# CurrentMetterLEDScreen.net
KiCad netlist of a schematic drawn in EAGLE
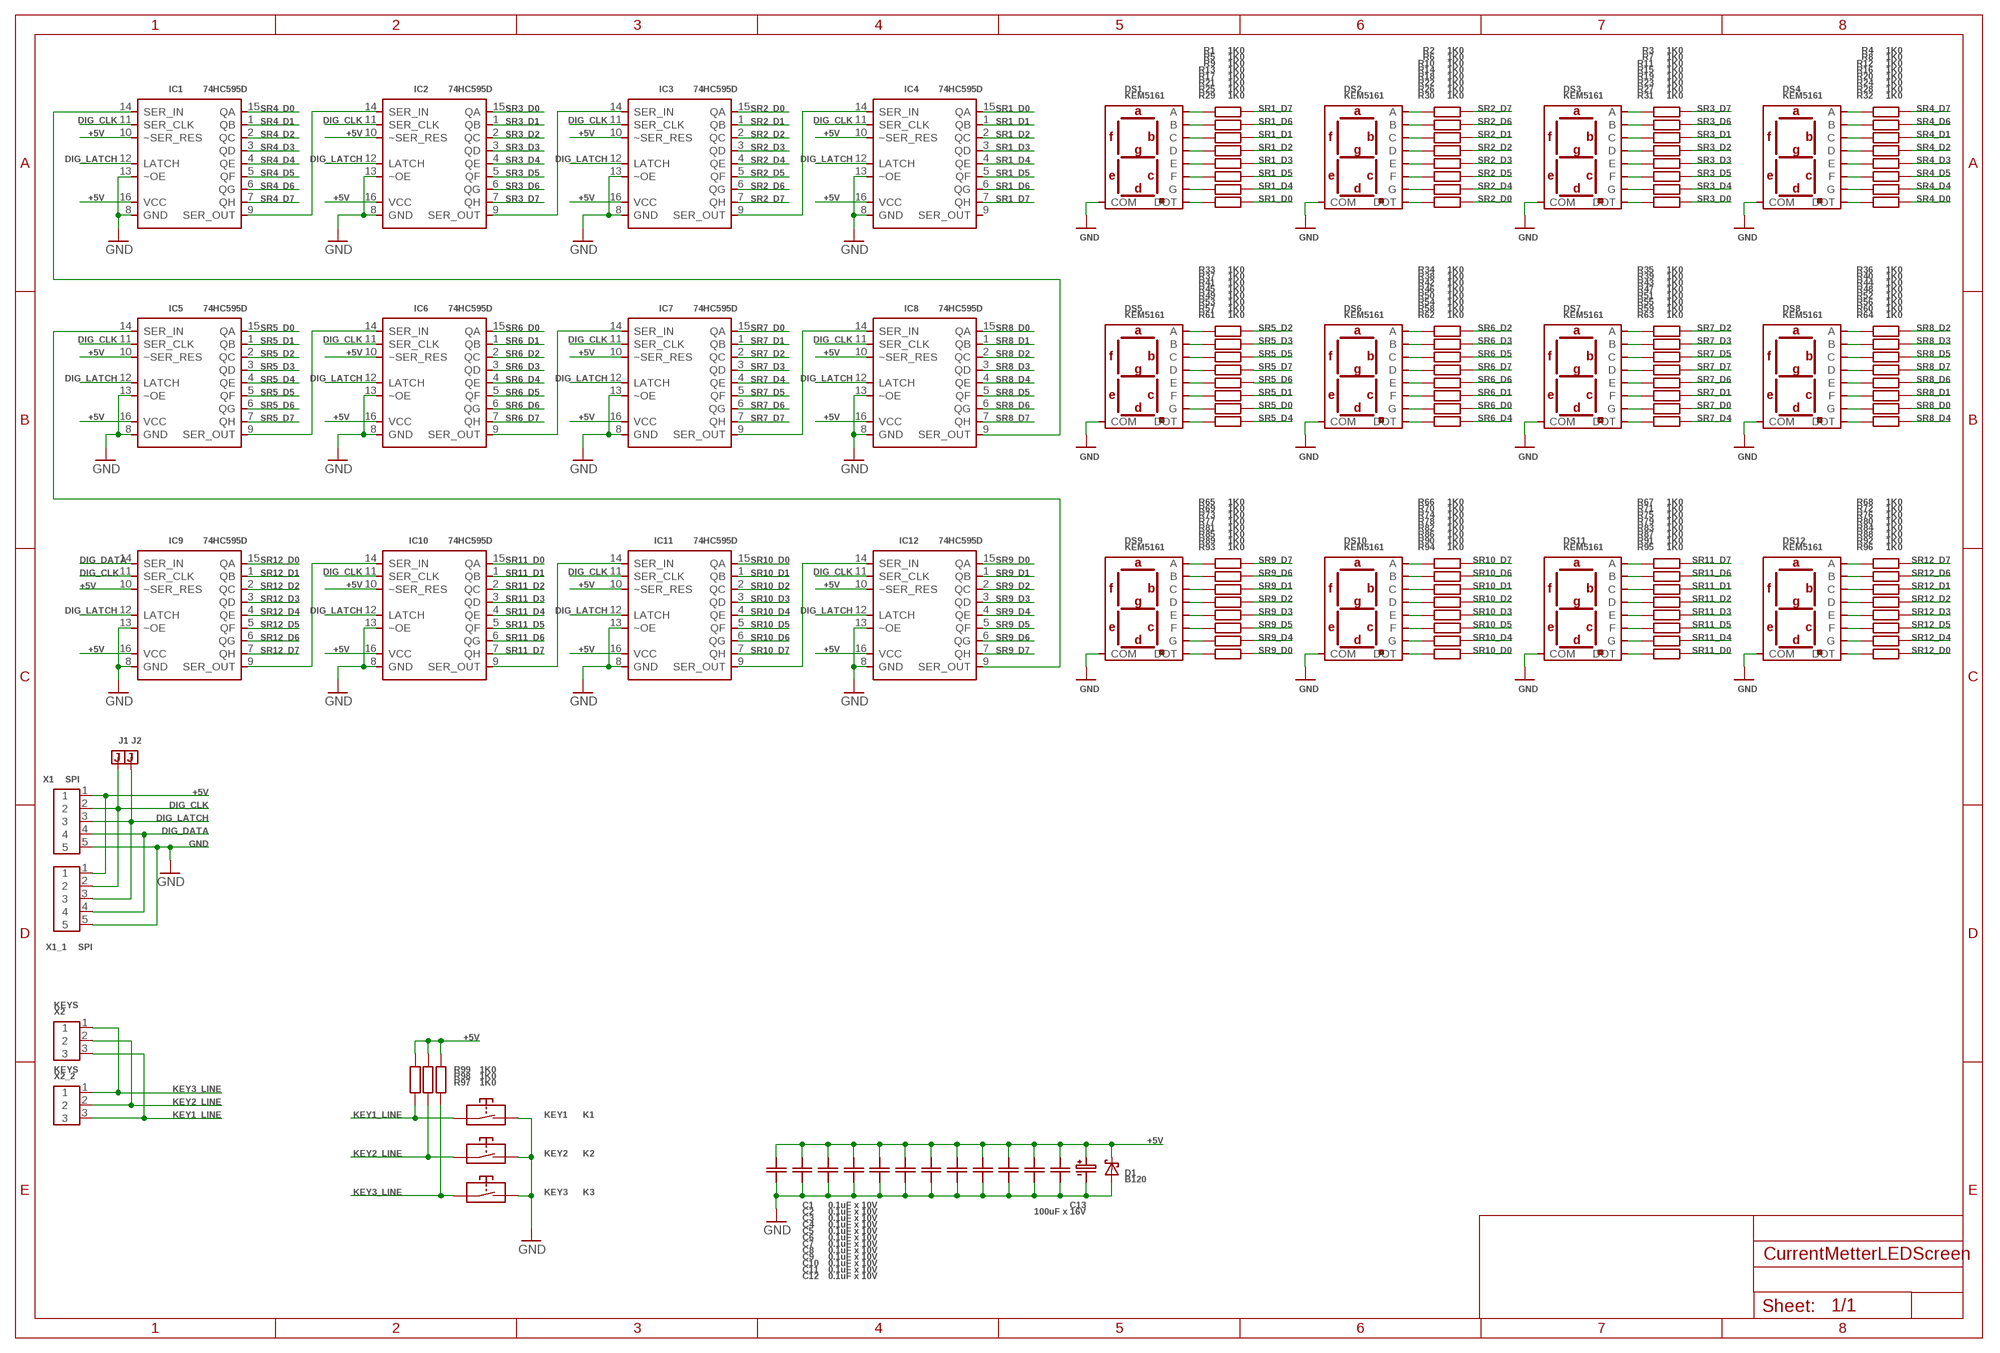
[diagram p0: schematic, sheet 1]

(export (version "E")
  (design (tool "Eeschema 10.0.6"))
  (components
    (comp (ref "C1")
      (value "0.1uF x 10V")
      (footprint "eagle-import:RSMD_0603")
      (libsource (lib "eagle-import") (part "CSMD_0603"))
    )
    (comp (ref "C2")
      (value "0.1uF x 10V")
      (footprint "eagle-import:RSMD_0603")
      (libsource (lib "eagle-import") (part "CSMD_0603"))
    )
    (comp (ref "C3")
      (value "0.1uF x 10V")
      (footprint "eagle-import:RSMD_0603")
      (libsource (lib "eagle-import") (part "CSMD_0603"))
    )
    (comp (ref "C4")
      (value "0.1uF x 10V")
      (footprint "eagle-import:RSMD_0603")
      (libsource (lib "eagle-import") (part "CSMD_0603"))
    )
    (comp (ref "C5")
      (value "0.1uF x 10V")
      (footprint "eagle-import:RSMD_0603")
      (libsource (lib "eagle-import") (part "CSMD_0603"))
    )
    (comp (ref "C6")
      (value "0.1uF x 10V")
      (footprint "eagle-import:RSMD_0603")
      (libsource (lib "eagle-import") (part "CSMD_0603"))
    )
    (comp (ref "C7")
      (value "0.1uF x 10V")
      (footprint "eagle-import:RSMD_0603")
      (libsource (lib "eagle-import") (part "CSMD_0603"))
    )
    (comp (ref "C8")
      (value "0.1uF x 10V")
      (footprint "eagle-import:RSMD_0603")
      (libsource (lib "eagle-import") (part "CSMD_0603"))
    )
    (comp (ref "C9")
      (value "0.1uF x 10V")
      (footprint "eagle-import:RSMD_0603")
      (libsource (lib "eagle-import") (part "CSMD_0603"))
    )
    (comp (ref "C10")
      (value "0.1uF x 10V")
      (footprint "eagle-import:RSMD_0603")
      (libsource (lib "eagle-import") (part "CSMD_0603"))
    )
    (comp (ref "C11")
      (value "0.1uF x 10V")
      (footprint "eagle-import:RSMD_0603")
      (libsource (lib "eagle-import") (part "CSMD_0603"))
    )
    (comp (ref "C12")
      (value "0.1uF x 10V")
      (footprint "eagle-import:RSMD_0603")
      (libsource (lib "eagle-import") (part "CSMD_0603"))
    )
    (comp (ref "C13")
      (value "100uF x 16V")
      (footprint "eagle-import:CE_6.3MM_HOR_REVERTED")
      (libsource (lib "eagle-import") (part "CE6.3MM_HOR_REVERTED"))
    )
    (comp (ref "D1")
      (value "B120")
      (footprint "eagle-import:DO-214AC")
      (libsource (lib "eagle-import") (part "B120(DO-214AC)"))
    )
    (comp (ref "DS1")
      (value "KEM5161")
      (footprint "eagle-import:KEM-5161(NARROW_PADS_OUTSIDE)")
      (libsource (lib "eagle-import") (part "KEM5161(NARROW_PADS_OUTSIDE)"))
    )
    (comp (ref "DS2")
      (value "KEM5161")
      (footprint "eagle-import:KEM-5161(NARROW_PADS_OUTSIDE)")
      (libsource (lib "eagle-import") (part "KEM5161(NARROW_PADS_OUTSIDE)"))
    )
    (comp (ref "DS3")
      (value "KEM5161")
      (footprint "eagle-import:KEM-5161(NARROW_PADS_OUTSIDE)")
      (libsource (lib "eagle-import") (part "KEM5161(NARROW_PADS_OUTSIDE)"))
    )
    (comp (ref "DS4")
      (value "KEM5161")
      (footprint "eagle-import:KEM-5161(NARROW_PADS_OUTSIDE)")
      (libsource (lib "eagle-import") (part "KEM5161(NARROW_PADS_OUTSIDE)"))
    )
    (comp (ref "DS5")
      (value "KEM5161")
      (footprint "eagle-import:KEM-5161(NARROW_PADS_OUTSIDE)")
      (libsource (lib "eagle-import") (part "KEM5161(NARROW_PADS_OUTSIDE)"))
    )
    (comp (ref "DS6")
      (value "KEM5161")
      (footprint "eagle-import:KEM-5161(NARROW_PADS_OUTSIDE)")
      (libsource (lib "eagle-import") (part "KEM5161(NARROW_PADS_OUTSIDE)"))
    )
    (comp (ref "DS7")
      (value "KEM5161")
      (footprint "eagle-import:KEM-5161(NARROW_PADS_OUTSIDE)")
      (libsource (lib "eagle-import") (part "KEM5161(NARROW_PADS_OUTSIDE)"))
    )
    (comp (ref "DS8")
      (value "KEM5161")
      (footprint "eagle-import:KEM-5161(NARROW_PADS_OUTSIDE)")
      (libsource (lib "eagle-import") (part "KEM5161(NARROW_PADS_OUTSIDE)"))
    )
    (comp (ref "DS9")
      (value "KEM5161")
      (footprint "eagle-import:KEM-5161(NARROW_PADS_OUTSIDE)")
      (libsource (lib "eagle-import") (part "KEM5161(NARROW_PADS_OUTSIDE)"))
    )
    (comp (ref "DS10")
      (value "KEM5161")
      (footprint "eagle-import:KEM-5161(NARROW_PADS_OUTSIDE)")
      (libsource (lib "eagle-import") (part "KEM5161(NARROW_PADS_OUTSIDE)"))
    )
    (comp (ref "DS11")
      (value "KEM5161")
      (footprint "eagle-import:KEM-5161(NARROW_PADS_OUTSIDE)")
      (libsource (lib "eagle-import") (part "KEM5161(NARROW_PADS_OUTSIDE)"))
    )
    (comp (ref "DS12")
      (value "KEM5161")
      (footprint "eagle-import:KEM-5161(NARROW_PADS_OUTSIDE)")
      (libsource (lib "eagle-import") (part "KEM5161(NARROW_PADS_OUTSIDE)"))
    )
    (comp (ref "IC1")
      (value "74HC595D")
      (footprint "eagle-import:SOIC16")
      (libsource (lib "eagle-import") (part "74HC595(SOIC16)"))
    )
    (comp (ref "IC2")
      (value "74HC595D")
      (footprint "eagle-import:SOIC16")
      (libsource (lib "eagle-import") (part "74HC595(SOIC16)"))
    )
    (comp (ref "IC3")
      (value "74HC595D")
      (footprint "eagle-import:SOIC16")
      (libsource (lib "eagle-import") (part "74HC595(SOIC16)"))
    )
    (comp (ref "IC4")
      (value "74HC595D")
      (footprint "eagle-import:SOIC16")
      (libsource (lib "eagle-import") (part "74HC595(SOIC16)"))
    )
    (comp (ref "IC5")
      (value "74HC595D")
      (footprint "eagle-import:SOIC16")
      (libsource (lib "eagle-import") (part "74HC595(SOIC16)"))
    )
    (comp (ref "IC6")
      (value "74HC595D")
      (footprint "eagle-import:SOIC16")
      (libsource (lib "eagle-import") (part "74HC595(SOIC16)"))
    )
    (comp (ref "IC7")
      (value "74HC595D")
      (footprint "eagle-import:SOIC16")
      (libsource (lib "eagle-import") (part "74HC595(SOIC16)"))
    )
    (comp (ref "IC8")
      (value "74HC595D")
      (footprint "eagle-import:SOIC16")
      (libsource (lib "eagle-import") (part "74HC595(SOIC16)"))
    )
    (comp (ref "IC9")
      (value "74HC595D")
      (footprint "eagle-import:SOIC16")
      (libsource (lib "eagle-import") (part "74HC595(SOIC16)"))
    )
    (comp (ref "IC10")
      (value "74HC595D")
      (footprint "eagle-import:SOIC16")
      (libsource (lib "eagle-import") (part "74HC595(SOIC16)"))
    )
    (comp (ref "IC11")
      (value "74HC595D")
      (footprint "eagle-import:SOIC16")
      (libsource (lib "eagle-import") (part "74HC595(SOIC16)"))
    )
    (comp (ref "IC12")
      (value "74HC595D")
      (footprint "eagle-import:SOIC16")
      (libsource (lib "eagle-import") (part "74HC595(SOIC16)"))
    )
    (comp (ref "J1")
      (value "JUMPER0805")
      (footprint "eagle-import:RSMD_0805")
      (libsource (lib "eagle-import") (part "JUMPER0805"))
    )
    (comp (ref "J2")
      (value "JUMPER0805")
      (footprint "eagle-import:RSMD_0805")
      (libsource (lib "eagle-import") (part "JUMPER0805"))
    )
    (comp (ref "KEY1")
      (value "K1")
      (footprint "eagle-import:KEY_7X4.5_BIG_PADS")
      (libsource (lib "eagle-import") (part "KEY(7X4.5_BIG_PADS)"))
    )
    (comp (ref "KEY2")
      (value "K2")
      (footprint "eagle-import:KEY_7X4.5_BIG_PADS")
      (libsource (lib "eagle-import") (part "KEY(7X4.5_BIG_PADS)"))
    )
    (comp (ref "KEY3")
      (value "K3")
      (footprint "eagle-import:KEY_7X4.5_BIG_PADS")
      (libsource (lib "eagle-import") (part "KEY(7X4.5_BIG_PADS)"))
    )
    (comp (ref "R1")
      (value "1K0")
      (footprint "eagle-import:RSMD_0603")
      (libsource (lib "eagle-import") (part "RSMD_0603"))
    )
    (comp (ref "R2")
      (value "1K0")
      (footprint "eagle-import:RSMD_0603")
      (libsource (lib "eagle-import") (part "RSMD_0603"))
    )
    (comp (ref "R3")
      (value "1K0")
      (footprint "eagle-import:RSMD_0603")
      (libsource (lib "eagle-import") (part "RSMD_0603"))
    )
    (comp (ref "R4")
      (value "1K0")
      (footprint "eagle-import:RSMD_0603")
      (libsource (lib "eagle-import") (part "RSMD_0603"))
    )
    (comp (ref "R5")
      (value "1K0")
      (footprint "eagle-import:RSMD_0603")
      (libsource (lib "eagle-import") (part "RSMD_0603"))
    )
    (comp (ref "R6")
      (value "1K0")
      (footprint "eagle-import:RSMD_0603")
      (libsource (lib "eagle-import") (part "RSMD_0603"))
    )
    (comp (ref "R7")
      (value "1K0")
      (footprint "eagle-import:RSMD_0603")
      (libsource (lib "eagle-import") (part "RSMD_0603"))
    )
    (comp (ref "R8")
      (value "1K0")
      (footprint "eagle-import:RSMD_0603")
      (libsource (lib "eagle-import") (part "RSMD_0603"))
    )
    (comp (ref "R9")
      (value "1K0")
      (footprint "eagle-import:RSMD_0603")
      (libsource (lib "eagle-import") (part "RSMD_0603"))
    )
    (comp (ref "R10")
      (value "1K0")
      (footprint "eagle-import:RSMD_0603")
      (libsource (lib "eagle-import") (part "RSMD_0603"))
    )
    (comp (ref "R11")
      (value "1K0")
      (footprint "eagle-import:RSMD_0603")
      (libsource (lib "eagle-import") (part "RSMD_0603"))
    )
    (comp (ref "R12")
      (value "1K0")
      (footprint "eagle-import:RSMD_0603")
      (libsource (lib "eagle-import") (part "RSMD_0603"))
    )
    (comp (ref "R13")
      (value "1K0")
      (footprint "eagle-import:RSMD_0603")
      (libsource (lib "eagle-import") (part "RSMD_0603"))
    )
    (comp (ref "R14")
      (value "1K0")
      (footprint "eagle-import:RSMD_0603")
      (libsource (lib "eagle-import") (part "RSMD_0603"))
    )
    (comp (ref "R15")
      (value "1K0")
      (footprint "eagle-import:RSMD_0603")
      (libsource (lib "eagle-import") (part "RSMD_0603"))
    )
    (comp (ref "R16")
      (value "1K0")
      (footprint "eagle-import:RSMD_0603")
      (libsource (lib "eagle-import") (part "RSMD_0603"))
    )
    (comp (ref "R17")
      (value "1K0")
      (footprint "eagle-import:RSMD_0603")
      (libsource (lib "eagle-import") (part "RSMD_0603"))
    )
    (comp (ref "R18")
      (value "1K0")
      (footprint "eagle-import:RSMD_0603")
      (libsource (lib "eagle-import") (part "RSMD_0603"))
    )
    (comp (ref "R19")
      (value "1K0")
      (footprint "eagle-import:RSMD_0603")
      (libsource (lib "eagle-import") (part "RSMD_0603"))
    )
    (comp (ref "R20")
      (value "1K0")
      (footprint "eagle-import:RSMD_0603")
      (libsource (lib "eagle-import") (part "RSMD_0603"))
    )
    (comp (ref "R21")
      (value "1K0")
      (footprint "eagle-import:RSMD_0603")
      (libsource (lib "eagle-import") (part "RSMD_0603"))
    )
    (comp (ref "R22")
      (value "1K0")
      (footprint "eagle-import:RSMD_0603")
      (libsource (lib "eagle-import") (part "RSMD_0603"))
    )
    (comp (ref "R23")
      (value "1K0")
      (footprint "eagle-import:RSMD_0603")
      (libsource (lib "eagle-import") (part "RSMD_0603"))
    )
    (comp (ref "R24")
      (value "1K0")
      (footprint "eagle-import:RSMD_0603")
      (libsource (lib "eagle-import") (part "RSMD_0603"))
    )
    (comp (ref "R25")
      (value "1K0")
      (footprint "eagle-import:RSMD_0603")
      (libsource (lib "eagle-import") (part "RSMD_0603"))
    )
    (comp (ref "R26")
      (value "1K0")
      (footprint "eagle-import:RSMD_0603")
      (libsource (lib "eagle-import") (part "RSMD_0603"))
    )
    (comp (ref "R27")
      (value "1K0")
      (footprint "eagle-import:RSMD_0603")
      (libsource (lib "eagle-import") (part "RSMD_0603"))
    )
    (comp (ref "R28")
      (value "1K0")
      (footprint "eagle-import:RSMD_0603")
      (libsource (lib "eagle-import") (part "RSMD_0603"))
    )
    (comp (ref "R29")
      (value "1K0")
      (footprint "eagle-import:RSMD_0603")
      (libsource (lib "eagle-import") (part "RSMD_0603"))
    )
    (comp (ref "R30")
      (value "1K0")
      (footprint "eagle-import:RSMD_0603")
      (libsource (lib "eagle-import") (part "RSMD_0603"))
    )
    (comp (ref "R31")
      (value "1K0")
      (footprint "eagle-import:RSMD_0603")
      (libsource (lib "eagle-import") (part "RSMD_0603"))
    )
    (comp (ref "R32")
      (value "1K0")
      (footprint "eagle-import:RSMD_0603")
      (libsource (lib "eagle-import") (part "RSMD_0603"))
    )
    (comp (ref "R33")
      (value "1K0")
      (footprint "eagle-import:RSMD_0603")
      (libsource (lib "eagle-import") (part "RSMD_0603"))
    )
    (comp (ref "R34")
      (value "1K0")
      (footprint "eagle-import:RSMD_0603")
      (libsource (lib "eagle-import") (part "RSMD_0603"))
    )
    (comp (ref "R35")
      (value "1K0")
      (footprint "eagle-import:RSMD_0603")
      (libsource (lib "eagle-import") (part "RSMD_0603"))
    )
    (comp (ref "R36")
      (value "1K0")
      (footprint "eagle-import:RSMD_0603")
      (libsource (lib "eagle-import") (part "RSMD_0603"))
    )
    (comp (ref "R37")
      (value "1K0")
      (footprint "eagle-import:RSMD_0603")
      (libsource (lib "eagle-import") (part "RSMD_0603"))
    )
    (comp (ref "R38")
      (value "1K0")
      (footprint "eagle-import:RSMD_0603")
      (libsource (lib "eagle-import") (part "RSMD_0603"))
    )
    (comp (ref "R39")
      (value "1K0")
      (footprint "eagle-import:RSMD_0603")
      (libsource (lib "eagle-import") (part "RSMD_0603"))
    )
    (comp (ref "R40")
      (value "1K0")
      (footprint "eagle-import:RSMD_0603")
      (libsource (lib "eagle-import") (part "RSMD_0603"))
    )
    (comp (ref "R41")
      (value "1K0")
      (footprint "eagle-import:RSMD_0603")
      (libsource (lib "eagle-import") (part "RSMD_0603"))
    )
    (comp (ref "R42")
      (value "1K0")
      (footprint "eagle-import:RSMD_0603")
      (libsource (lib "eagle-import") (part "RSMD_0603"))
    )
    (comp (ref "R43")
      (value "1K0")
      (footprint "eagle-import:RSMD_0603")
      (libsource (lib "eagle-import") (part "RSMD_0603"))
    )
    (comp (ref "R44")
      (value "1K0")
      (footprint "eagle-import:RSMD_0603")
      (libsource (lib "eagle-import") (part "RSMD_0603"))
    )
    (comp (ref "R45")
      (value "1K0")
      (footprint "eagle-import:RSMD_0603")
      (libsource (lib "eagle-import") (part "RSMD_0603"))
    )
    (comp (ref "R46")
      (value "1K0")
      (footprint "eagle-import:RSMD_0603")
      (libsource (lib "eagle-import") (part "RSMD_0603"))
    )
    (comp (ref "R47")
      (value "1K0")
      (footprint "eagle-import:RSMD_0603")
      (libsource (lib "eagle-import") (part "RSMD_0603"))
    )
    (comp (ref "R48")
      (value "1K0")
      (footprint "eagle-import:RSMD_0603")
      (libsource (lib "eagle-import") (part "RSMD_0603"))
    )
    (comp (ref "R49")
      (value "1K0")
      (footprint "eagle-import:RSMD_0603")
      (libsource (lib "eagle-import") (part "RSMD_0603"))
    )
    (comp (ref "R50")
      (value "1K0")
      (footprint "eagle-import:RSMD_0603")
      (libsource (lib "eagle-import") (part "RSMD_0603"))
    )
    (comp (ref "R51")
      (value "1K0")
      (footprint "eagle-import:RSMD_0603")
      (libsource (lib "eagle-import") (part "RSMD_0603"))
    )
    (comp (ref "R52")
      (value "1K0")
      (footprint "eagle-import:RSMD_0603")
      (libsource (lib "eagle-import") (part "RSMD_0603"))
    )
    (comp (ref "R53")
      (value "1K0")
      (footprint "eagle-import:RSMD_0603")
      (libsource (lib "eagle-import") (part "RSMD_0603"))
    )
    (comp (ref "R54")
      (value "1K0")
      (footprint "eagle-import:RSMD_0603")
      (libsource (lib "eagle-import") (part "RSMD_0603"))
    )
    (comp (ref "R55")
      (value "1K0")
      (footprint "eagle-import:RSMD_0603")
      (libsource (lib "eagle-import") (part "RSMD_0603"))
    )
    (comp (ref "R56")
      (value "1K0")
      (footprint "eagle-import:RSMD_0603")
      (libsource (lib "eagle-import") (part "RSMD_0603"))
    )
    (comp (ref "R57")
      (value "1K0")
      (footprint "eagle-import:RSMD_0603")
      (libsource (lib "eagle-import") (part "RSMD_0603"))
    )
    (comp (ref "R58")
      (value "1K0")
      (footprint "eagle-import:RSMD_0603")
      (libsource (lib "eagle-import") (part "RSMD_0603"))
    )
    (comp (ref "R59")
      (value "1K0")
      (footprint "eagle-import:RSMD_0603")
      (libsource (lib "eagle-import") (part "RSMD_0603"))
    )
    (comp (ref "R60")
      (value "1K0")
      (footprint "eagle-import:RSMD_0603")
      (libsource (lib "eagle-import") (part "RSMD_0603"))
    )
    (comp (ref "R61")
      (value "1K0")
      (footprint "eagle-import:RSMD_0603")
      (libsource (lib "eagle-import") (part "RSMD_0603"))
    )
    (comp (ref "R62")
      (value "1K0")
      (footprint "eagle-import:RSMD_0603")
      (libsource (lib "eagle-import") (part "RSMD_0603"))
    )
    (comp (ref "R63")
      (value "1K0")
      (footprint "eagle-import:RSMD_0603")
      (libsource (lib "eagle-import") (part "RSMD_0603"))
    )
    (comp (ref "R64")
      (value "1K0")
      (footprint "eagle-import:RSMD_0603")
      (libsource (lib "eagle-import") (part "RSMD_0603"))
    )
    (comp (ref "R65")
      (value "1K0")
      (footprint "eagle-import:RSMD_0603")
      (libsource (lib "eagle-import") (part "RSMD_0603"))
    )
    (comp (ref "R66")
      (value "1K0")
      (footprint "eagle-import:RSMD_0603")
      (libsource (lib "eagle-import") (part "RSMD_0603"))
    )
    (comp (ref "R67")
      (value "1K0")
      (footprint "eagle-import:RSMD_0603")
      (libsource (lib "eagle-import") (part "RSMD_0603"))
    )
    (comp (ref "R68")
      (value "1K0")
      (footprint "eagle-import:RSMD_0603")
      (libsource (lib "eagle-import") (part "RSMD_0603"))
    )
    (comp (ref "R69")
      (value "1K0")
      (footprint "eagle-import:RSMD_0603")
      (libsource (lib "eagle-import") (part "RSMD_0603"))
    )
    (comp (ref "R70")
      (value "1K0")
      (footprint "eagle-import:RSMD_0603")
      (libsource (lib "eagle-import") (part "RSMD_0603"))
    )
    (comp (ref "R71")
      (value "1K0")
      (footprint "eagle-import:RSMD_0603")
      (libsource (lib "eagle-import") (part "RSMD_0603"))
    )
    (comp (ref "R72")
      (value "1K0")
      (footprint "eagle-import:RSMD_0603")
      (libsource (lib "eagle-import") (part "RSMD_0603"))
    )
    (comp (ref "R73")
      (value "1K0")
      (footprint "eagle-import:RSMD_0603")
      (libsource (lib "eagle-import") (part "RSMD_0603"))
    )
    (comp (ref "R74")
      (value "1K0")
      (footprint "eagle-import:RSMD_0603")
      (libsource (lib "eagle-import") (part "RSMD_0603"))
    )
    (comp (ref "R75")
      (value "1K0")
      (footprint "eagle-import:RSMD_0603")
      (libsource (lib "eagle-import") (part "RSMD_0603"))
    )
    (comp (ref "R76")
      (value "1K0")
      (footprint "eagle-import:RSMD_0603")
      (libsource (lib "eagle-import") (part "RSMD_0603"))
    )
    (comp (ref "R77")
      (value "1K0")
      (footprint "eagle-import:RSMD_0603")
      (libsource (lib "eagle-import") (part "RSMD_0603"))
    )
    (comp (ref "R78")
      (value "1K0")
      (footprint "eagle-import:RSMD_0603")
      (libsource (lib "eagle-import") (part "RSMD_0603"))
    )
    (comp (ref "R79")
      (value "1K0")
      (footprint "eagle-import:RSMD_0603")
      (libsource (lib "eagle-import") (part "RSMD_0603"))
    )
    (comp (ref "R80")
      (value "1K0")
      (footprint "eagle-import:RSMD_0603")
      (libsource (lib "eagle-import") (part "RSMD_0603"))
    )
    (comp (ref "R81")
      (value "1K0")
      (footprint "eagle-import:RSMD_0603")
      (libsource (lib "eagle-import") (part "RSMD_0603"))
    )
    (comp (ref "R82")
      (value "1K0")
      (footprint "eagle-import:RSMD_0603")
      (libsource (lib "eagle-import") (part "RSMD_0603"))
    )
    (comp (ref "R83")
      (value "1K0")
      (footprint "eagle-import:RSMD_0603")
      (libsource (lib "eagle-import") (part "RSMD_0603"))
    )
    (comp (ref "R84")
      (value "1K0")
      (footprint "eagle-import:RSMD_0603")
      (libsource (lib "eagle-import") (part "RSMD_0603"))
    )
    (comp (ref "R85")
      (value "1K0")
      (footprint "eagle-import:RSMD_0603")
      (libsource (lib "eagle-import") (part "RSMD_0603"))
    )
    (comp (ref "R86")
      (value "1K0")
      (footprint "eagle-import:RSMD_0603")
      (libsource (lib "eagle-import") (part "RSMD_0603"))
    )
    (comp (ref "R87")
      (value "1K0")
      (footprint "eagle-import:RSMD_0603")
      (libsource (lib "eagle-import") (part "RSMD_0603"))
    )
    (comp (ref "R88")
      (value "1K0")
      (footprint "eagle-import:RSMD_0603")
      (libsource (lib "eagle-import") (part "RSMD_0603"))
    )
    (comp (ref "R89")
      (value "1K0")
      (footprint "eagle-import:RSMD_0603")
      (libsource (lib "eagle-import") (part "RSMD_0603"))
    )
    (comp (ref "R90")
      (value "1K0")
      (footprint "eagle-import:RSMD_0603")
      (libsource (lib "eagle-import") (part "RSMD_0603"))
    )
    (comp (ref "R91")
      (value "1K0")
      (footprint "eagle-import:RSMD_0603")
      (libsource (lib "eagle-import") (part "RSMD_0603"))
    )
    (comp (ref "R92")
      (value "1K0")
      (footprint "eagle-import:RSMD_0603")
      (libsource (lib "eagle-import") (part "RSMD_0603"))
    )
    (comp (ref "R93")
      (value "1K0")
      (footprint "eagle-import:RSMD_0603")
      (libsource (lib "eagle-import") (part "RSMD_0603"))
    )
    (comp (ref "R94")
      (value "1K0")
      (footprint "eagle-import:RSMD_0603")
      (libsource (lib "eagle-import") (part "RSMD_0603"))
    )
    (comp (ref "R95")
      (value "1K0")
      (footprint "eagle-import:RSMD_0603")
      (libsource (lib "eagle-import") (part "RSMD_0603"))
    )
    (comp (ref "R96")
      (value "1K0")
      (footprint "eagle-import:RSMD_0603")
      (libsource (lib "eagle-import") (part "RSMD_0603"))
    )
    (comp (ref "R97")
      (value "1K0")
      (footprint "eagle-import:RSMD_0603")
      (libsource (lib "eagle-import") (part "RSMD_0603"))
    )
    (comp (ref "R98")
      (value "1K0")
      (footprint "eagle-import:RSMD_0603")
      (libsource (lib "eagle-import") (part "RSMD_0603"))
    )
    (comp (ref "R99")
      (value "1K0")
      (footprint "eagle-import:RSMD_0603")
      (libsource (lib "eagle-import") (part "RSMD_0603"))
    )
    (comp (ref "X1")
      (value "SPI")
      (footprint "eagle-import:PIN5X1_2.54MM_SIDE_BOARD")
      (libsource (lib "eagle-import") (part "PIN1X5(2.54_SIDE_BOARD)"))
    )
    (comp (ref "X1_1")
      (value "SPI")
      (footprint "eagle-import:PIN5X1_2.54MM_WITH_CLAMP")
      (libsource (lib "eagle-import") (part "PIN1X5(2.54_VERT_CLAMP)"))
    )
    (comp (ref "X2")
      (value "KEYS")
      (footprint "eagle-import:PIN1X3_2.54MM_SIDE_BOARD")
      (libsource (lib "eagle-import") (part "PIN1X3(2.54MM_SIDE_BOARD)"))
    )
    (comp (ref "X2_2")
      (value "KEYS")
      (footprint "eagle-import:PIN3X1_2.54MM_WITH_CLAMP")
      (libsource (lib "eagle-import") (part "PIN1X3(2.54MM_WITH_CLAMP)"))
    )
  )
  (nets
    (net (code "1") (name "/+5V") (class "Default")
      (node (ref "C1") (pin "PAD_1") (pinfunction "PIN1_PAD_1") (pintype "bidirectional"))
      (node (ref "C10") (pin "PAD_1") (pinfunction "PIN1_PAD_1") (pintype "bidirectional"))
      (node (ref "C11") (pin "PAD_1") (pinfunction "PIN1_PAD_1") (pintype "bidirectional"))
      (node (ref "C12") (pin "PAD_1") (pinfunction "PIN1_PAD_1") (pintype "bidirectional"))
      (node (ref "C13") (pin "PLUS") (pinfunction "PLUS_PLUS") (pintype "bidirectional"))
      (node (ref "C2") (pin "PAD_1") (pinfunction "PIN1_PAD_1") (pintype "bidirectional"))
      (node (ref "C3") (pin "PAD_1") (pinfunction "PIN1_PAD_1") (pintype "bidirectional"))
      (node (ref "C4") (pin "PAD_1") (pinfunction "PIN1_PAD_1") (pintype "bidirectional"))
      (node (ref "C5") (pin "PAD_1") (pinfunction "PIN1_PAD_1") (pintype "bidirectional"))
      (node (ref "C6") (pin "PAD_1") (pinfunction "PIN1_PAD_1") (pintype "bidirectional"))
      (node (ref "C7") (pin "PAD_1") (pinfunction "PIN1_PAD_1") (pintype "bidirectional"))
      (node (ref "C8") (pin "PAD_1") (pinfunction "PIN1_PAD_1") (pintype "bidirectional"))
      (node (ref "C9") (pin "PAD_1") (pinfunction "PIN1_PAD_1") (pintype "bidirectional"))
      (node (ref "D1") (pin "CATHODE") (pinfunction "CATHODE_CATHODE") (pintype "passive"))
      (node (ref "IC1") (pin "10") (pinfunction "~{SER_RES}_10") (pintype "bidirectional"))
      (node (ref "IC1") (pin "16") (pinfunction "VCC_16") (pintype "bidirectional"))
      (node (ref "IC10") (pin "10") (pinfunction "~{SER_RES}_10") (pintype "bidirectional"))
      (node (ref "IC10") (pin "16") (pinfunction "VCC_16") (pintype "bidirectional"))
      (node (ref "IC11") (pin "10") (pinfunction "~{SER_RES}_10") (pintype "bidirectional"))
      (node (ref "IC11") (pin "16") (pinfunction "VCC_16") (pintype "bidirectional"))
      (node (ref "IC12") (pin "10") (pinfunction "~{SER_RES}_10") (pintype "bidirectional"))
      (node (ref "IC12") (pin "16") (pinfunction "VCC_16") (pintype "bidirectional"))
      (node (ref "IC2") (pin "10") (pinfunction "~{SER_RES}_10") (pintype "bidirectional"))
      (node (ref "IC2") (pin "16") (pinfunction "VCC_16") (pintype "bidirectional"))
      (node (ref "IC3") (pin "10") (pinfunction "~{SER_RES}_10") (pintype "bidirectional"))
      (node (ref "IC3") (pin "16") (pinfunction "VCC_16") (pintype "bidirectional"))
      (node (ref "IC4") (pin "10") (pinfunction "~{SER_RES}_10") (pintype "bidirectional"))
      (node (ref "IC4") (pin "16") (pinfunction "VCC_16") (pintype "bidirectional"))
      (node (ref "IC5") (pin "10") (pinfunction "~{SER_RES}_10") (pintype "bidirectional"))
      (node (ref "IC5") (pin "16") (pinfunction "VCC_16") (pintype "bidirectional"))
      (node (ref "IC6") (pin "10") (pinfunction "~{SER_RES}_10") (pintype "bidirectional"))
      (node (ref "IC6") (pin "16") (pinfunction "VCC_16") (pintype "bidirectional"))
      (node (ref "IC7") (pin "10") (pinfunction "~{SER_RES}_10") (pintype "bidirectional"))
      (node (ref "IC7") (pin "16") (pinfunction "VCC_16") (pintype "bidirectional"))
      (node (ref "IC8") (pin "10") (pinfunction "~{SER_RES}_10") (pintype "bidirectional"))
      (node (ref "IC8") (pin "16") (pinfunction "VCC_16") (pintype "bidirectional"))
      (node (ref "IC9") (pin "10") (pinfunction "~{SER_RES}_10") (pintype "bidirectional"))
      (node (ref "IC9") (pin "16") (pinfunction "VCC_16") (pintype "bidirectional"))
      (node (ref "R97") (pin "PAD_1") (pinfunction "PIN1_PAD_1") (pintype "passive"))
      (node (ref "R98") (pin "PAD_1") (pinfunction "PIN1_PAD_1") (pintype "passive"))
      (node (ref "R99") (pin "PAD_1") (pinfunction "PIN1_PAD_1") (pintype "passive"))
      (node (ref "X1") (pin "1") (pinfunction "1_1") (pintype "passive"))
      (node (ref "X1_1") (pin "1") (pinfunction "1_1") (pintype "passive"))
    )
    (net (code "2") (name "/DIG_CLK") (class "Default")
      (node (ref "IC1") (pin "11") (pinfunction "SER_CLK_11") (pintype "bidirectional"))
      (node (ref "IC10") (pin "11") (pinfunction "SER_CLK_11") (pintype "bidirectional"))
      (node (ref "IC11") (pin "11") (pinfunction "SER_CLK_11") (pintype "bidirectional"))
      (node (ref "IC12") (pin "11") (pinfunction "SER_CLK_11") (pintype "bidirectional"))
      (node (ref "IC2") (pin "11") (pinfunction "SER_CLK_11") (pintype "bidirectional"))
      (node (ref "IC3") (pin "11") (pinfunction "SER_CLK_11") (pintype "bidirectional"))
      (node (ref "IC4") (pin "11") (pinfunction "SER_CLK_11") (pintype "bidirectional"))
      (node (ref "IC5") (pin "11") (pinfunction "SER_CLK_11") (pintype "bidirectional"))
      (node (ref "IC6") (pin "11") (pinfunction "SER_CLK_11") (pintype "bidirectional"))
      (node (ref "IC7") (pin "11") (pinfunction "SER_CLK_11") (pintype "bidirectional"))
      (node (ref "IC8") (pin "11") (pinfunction "SER_CLK_11") (pintype "bidirectional"))
      (node (ref "IC9") (pin "11") (pinfunction "SER_CLK_11") (pintype "bidirectional"))
      (node (ref "J1") (pin "PAD_0") (pinfunction "PIN1_PAD_0") (pintype "passive"))
      (node (ref "J1") (pin "PAD_1") (pinfunction "PIN1_PAD_1") (pintype "passive"))
      (node (ref "X1") (pin "2") (pinfunction "2_2") (pintype "passive"))
      (node (ref "X1_1") (pin "2") (pinfunction "2_2") (pintype "passive"))
    )
    (net (code "3") (name "/DIG_DATA") (class "Default")
      (node (ref "IC9") (pin "14") (pinfunction "SER_IN_14") (pintype "bidirectional"))
      (node (ref "X1") (pin "4") (pinfunction "4_4") (pintype "passive"))
      (node (ref "X1_1") (pin "4") (pinfunction "4_4") (pintype "passive"))
    )
    (net (code "4") (name "/DIG_LATCH") (class "Default")
      (node (ref "IC1") (pin "12") (pinfunction "LATCH_12") (pintype "bidirectional"))
      (node (ref "IC10") (pin "12") (pinfunction "LATCH_12") (pintype "bidirectional"))
      (node (ref "IC11") (pin "12") (pinfunction "LATCH_12") (pintype "bidirectional"))
      (node (ref "IC12") (pin "12") (pinfunction "LATCH_12") (pintype "bidirectional"))
      (node (ref "IC2") (pin "12") (pinfunction "LATCH_12") (pintype "bidirectional"))
      (node (ref "IC3") (pin "12") (pinfunction "LATCH_12") (pintype "bidirectional"))
      (node (ref "IC4") (pin "12") (pinfunction "LATCH_12") (pintype "bidirectional"))
      (node (ref "IC5") (pin "12") (pinfunction "LATCH_12") (pintype "bidirectional"))
      (node (ref "IC6") (pin "12") (pinfunction "LATCH_12") (pintype "bidirectional"))
      (node (ref "IC7") (pin "12") (pinfunction "LATCH_12") (pintype "bidirectional"))
      (node (ref "IC8") (pin "12") (pinfunction "LATCH_12") (pintype "bidirectional"))
      (node (ref "IC9") (pin "12") (pinfunction "LATCH_12") (pintype "bidirectional"))
      (node (ref "J2") (pin "PAD_0") (pinfunction "PIN1_PAD_0") (pintype "passive"))
      (node (ref "J2") (pin "PAD_1") (pinfunction "PIN1_PAD_1") (pintype "passive"))
      (node (ref "X1") (pin "3") (pinfunction "3_3") (pintype "passive"))
      (node (ref "X1_1") (pin "3") (pinfunction "3_3") (pintype "passive"))
    )
    (net (code "5") (name "/KEY1_LINE") (class "Default")
      (node (ref "KEY1") (pin "1") (pinfunction "1_1") (pintype "bidirectional"))
      (node (ref "KEY1") (pin "2") (pinfunction "1_2") (pintype "bidirectional"))
      (node (ref "R99") (pin "PAD_0") (pinfunction "PIN0_PAD_0") (pintype "passive"))
      (node (ref "X2") (pin "3") (pinfunction "3_3") (pintype "passive"))
      (node (ref "X2_2") (pin "3") (pinfunction "3_3") (pintype "passive"))
    )
    (net (code "6") (name "/KEY2_LINE") (class "Default")
      (node (ref "KEY2") (pin "1") (pinfunction "1_1") (pintype "bidirectional"))
      (node (ref "KEY2") (pin "2") (pinfunction "1_2") (pintype "bidirectional"))
      (node (ref "R98") (pin "PAD_0") (pinfunction "PIN0_PAD_0") (pintype "passive"))
      (node (ref "X2") (pin "2") (pinfunction "2_2") (pintype "passive"))
      (node (ref "X2_2") (pin "2") (pinfunction "2_2") (pintype "passive"))
    )
    (net (code "7") (name "/KEY3_LINE") (class "Default")
      (node (ref "KEY3") (pin "1") (pinfunction "1_1") (pintype "bidirectional"))
      (node (ref "KEY3") (pin "2") (pinfunction "1_2") (pintype "bidirectional"))
      (node (ref "R97") (pin "PAD_0") (pinfunction "PIN0_PAD_0") (pintype "passive"))
      (node (ref "X2") (pin "1") (pinfunction "1_1") (pintype "passive"))
      (node (ref "X2_2") (pin "1") (pinfunction "1_1") (pintype "passive"))
    )
    (net (code "8") (name "/SR1_D0") (class "Default")
      (node (ref "IC4") (pin "15") (pinfunction "QA_15") (pintype "bidirectional"))
      (node (ref "R29") (pin "PAD_1") (pinfunction "PIN1_PAD_1") (pintype "passive"))
    )
    (net (code "9") (name "/SR1_D1") (class "Default")
      (node (ref "IC4") (pin "1") (pinfunction "QB_1") (pintype "bidirectional"))
      (node (ref "R9") (pin "PAD_1") (pinfunction "PIN1_PAD_1") (pintype "passive"))
    )
    (net (code "10") (name "/SR1_D2") (class "Default")
      (node (ref "IC4") (pin "2") (pinfunction "QC_2") (pintype "bidirectional"))
      (node (ref "R13") (pin "PAD_1") (pinfunction "PIN1_PAD_1") (pintype "passive"))
    )
    (net (code "11") (name "/SR1_D3") (class "Default")
      (node (ref "IC4") (pin "3") (pinfunction "QD_3") (pintype "bidirectional"))
      (node (ref "R17") (pin "PAD_1") (pinfunction "PIN1_PAD_1") (pintype "passive"))
    )
    (net (code "12") (name "/SR1_D4") (class "Default")
      (node (ref "IC4") (pin "4") (pinfunction "QE_4") (pintype "bidirectional"))
      (node (ref "R25") (pin "PAD_1") (pinfunction "PIN1_PAD_1") (pintype "passive"))
    )
    (net (code "13") (name "/SR1_D5") (class "Default")
      (node (ref "IC4") (pin "5") (pinfunction "QF_5") (pintype "bidirectional"))
      (node (ref "R21") (pin "PAD_1") (pinfunction "PIN1_PAD_1") (pintype "passive"))
    )
    (net (code "14") (name "/SR1_D6") (class "Default")
      (node (ref "IC4") (pin "6") (pinfunction "QG_6") (pintype "bidirectional"))
      (node (ref "R5") (pin "PAD_1") (pinfunction "PIN1_PAD_1") (pintype "passive"))
    )
    (net (code "15") (name "/SR1_D7") (class "Default")
      (node (ref "IC4") (pin "7") (pinfunction "QH_7") (pintype "bidirectional"))
      (node (ref "R1") (pin "PAD_1") (pinfunction "PIN1_PAD_1") (pintype "passive"))
    )
    (net (code "16") (name "/SR2_D0") (class "Default")
      (node (ref "IC3") (pin "15") (pinfunction "QA_15") (pintype "bidirectional"))
      (node (ref "R30") (pin "PAD_1") (pinfunction "PIN1_PAD_1") (pintype "passive"))
    )
    (net (code "17") (name "/SR2_D1") (class "Default")
      (node (ref "IC3") (pin "1") (pinfunction "QB_1") (pintype "bidirectional"))
      (node (ref "R10") (pin "PAD_1") (pinfunction "PIN1_PAD_1") (pintype "passive"))
    )
    (net (code "18") (name "/SR2_D2") (class "Default")
      (node (ref "IC3") (pin "2") (pinfunction "QC_2") (pintype "bidirectional"))
      (node (ref "R14") (pin "PAD_1") (pinfunction "PIN1_PAD_1") (pintype "passive"))
    )
    (net (code "19") (name "/SR2_D3") (class "Default")
      (node (ref "IC3") (pin "3") (pinfunction "QD_3") (pintype "bidirectional"))
      (node (ref "R18") (pin "PAD_1") (pinfunction "PIN1_PAD_1") (pintype "passive"))
    )
    (net (code "20") (name "/SR2_D4") (class "Default")
      (node (ref "IC3") (pin "4") (pinfunction "QE_4") (pintype "bidirectional"))
      (node (ref "R26") (pin "PAD_1") (pinfunction "PIN1_PAD_1") (pintype "passive"))
    )
    (net (code "21") (name "/SR2_D5") (class "Default")
      (node (ref "IC3") (pin "5") (pinfunction "QF_5") (pintype "bidirectional"))
      (node (ref "R22") (pin "PAD_1") (pinfunction "PIN1_PAD_1") (pintype "passive"))
    )
    (net (code "22") (name "/SR2_D6") (class "Default")
      (node (ref "IC3") (pin "6") (pinfunction "QG_6") (pintype "bidirectional"))
      (node (ref "R6") (pin "PAD_1") (pinfunction "PIN1_PAD_1") (pintype "passive"))
    )
    (net (code "23") (name "/SR2_D7") (class "Default")
      (node (ref "IC3") (pin "7") (pinfunction "QH_7") (pintype "bidirectional"))
      (node (ref "R2") (pin "PAD_1") (pinfunction "PIN1_PAD_1") (pintype "passive"))
    )
    (net (code "24") (name "/SR3_D0") (class "Default")
      (node (ref "IC2") (pin "15") (pinfunction "QA_15") (pintype "bidirectional"))
      (node (ref "R31") (pin "PAD_1") (pinfunction "PIN1_PAD_1") (pintype "passive"))
    )
    (net (code "25") (name "/SR3_D1") (class "Default")
      (node (ref "IC2") (pin "1") (pinfunction "QB_1") (pintype "bidirectional"))
      (node (ref "R11") (pin "PAD_1") (pinfunction "PIN1_PAD_1") (pintype "passive"))
    )
    (net (code "26") (name "/SR3_D2") (class "Default")
      (node (ref "IC2") (pin "2") (pinfunction "QC_2") (pintype "bidirectional"))
      (node (ref "R15") (pin "PAD_1") (pinfunction "PIN1_PAD_1") (pintype "passive"))
    )
    (net (code "27") (name "/SR3_D3") (class "Default")
      (node (ref "IC2") (pin "3") (pinfunction "QD_3") (pintype "bidirectional"))
      (node (ref "R19") (pin "PAD_1") (pinfunction "PIN1_PAD_1") (pintype "passive"))
    )
    (net (code "28") (name "/SR3_D4") (class "Default")
      (node (ref "IC2") (pin "4") (pinfunction "QE_4") (pintype "bidirectional"))
      (node (ref "R27") (pin "PAD_1") (pinfunction "PIN1_PAD_1") (pintype "passive"))
    )
    (net (code "29") (name "/SR3_D5") (class "Default")
      (node (ref "IC2") (pin "5") (pinfunction "QF_5") (pintype "bidirectional"))
      (node (ref "R23") (pin "PAD_1") (pinfunction "PIN1_PAD_1") (pintype "passive"))
    )
    (net (code "30") (name "/SR3_D6") (class "Default")
      (node (ref "IC2") (pin "6") (pinfunction "QG_6") (pintype "bidirectional"))
      (node (ref "R7") (pin "PAD_1") (pinfunction "PIN1_PAD_1") (pintype "passive"))
    )
    (net (code "31") (name "/SR3_D7") (class "Default")
      (node (ref "IC2") (pin "7") (pinfunction "QH_7") (pintype "bidirectional"))
      (node (ref "R3") (pin "PAD_1") (pinfunction "PIN1_PAD_1") (pintype "passive"))
    )
    (net (code "32") (name "/SR4_D0") (class "Default")
      (node (ref "IC1") (pin "15") (pinfunction "QA_15") (pintype "bidirectional"))
      (node (ref "R32") (pin "PAD_1") (pinfunction "PIN1_PAD_1") (pintype "passive"))
    )
    (net (code "33") (name "/SR4_D1") (class "Default")
      (node (ref "IC1") (pin "1") (pinfunction "QB_1") (pintype "bidirectional"))
      (node (ref "R12") (pin "PAD_1") (pinfunction "PIN1_PAD_1") (pintype "passive"))
    )
    (net (code "34") (name "/SR4_D2") (class "Default")
      (node (ref "IC1") (pin "2") (pinfunction "QC_2") (pintype "bidirectional"))
      (node (ref "R16") (pin "PAD_1") (pinfunction "PIN1_PAD_1") (pintype "passive"))
    )
    (net (code "35") (name "/SR4_D3") (class "Default")
      (node (ref "IC1") (pin "3") (pinfunction "QD_3") (pintype "bidirectional"))
      (node (ref "R20") (pin "PAD_1") (pinfunction "PIN1_PAD_1") (pintype "passive"))
    )
    (net (code "36") (name "/SR4_D4") (class "Default")
      (node (ref "IC1") (pin "4") (pinfunction "QE_4") (pintype "bidirectional"))
      (node (ref "R28") (pin "PAD_1") (pinfunction "PIN1_PAD_1") (pintype "passive"))
    )
    (net (code "37") (name "/SR4_D5") (class "Default")
      (node (ref "IC1") (pin "5") (pinfunction "QF_5") (pintype "bidirectional"))
      (node (ref "R24") (pin "PAD_1") (pinfunction "PIN1_PAD_1") (pintype "passive"))
    )
    (net (code "38") (name "/SR4_D6") (class "Default")
      (node (ref "IC1") (pin "6") (pinfunction "QG_6") (pintype "bidirectional"))
      (node (ref "R8") (pin "PAD_1") (pinfunction "PIN1_PAD_1") (pintype "passive"))
    )
    (net (code "39") (name "/SR4_D7") (class "Default")
      (node (ref "IC1") (pin "7") (pinfunction "QH_7") (pintype "bidirectional"))
      (node (ref "R4") (pin "PAD_1") (pinfunction "PIN1_PAD_1") (pintype "passive"))
    )
    (net (code "40") (name "/SR5_D0") (class "Default")
      (node (ref "IC5") (pin "15") (pinfunction "QA_15") (pintype "bidirectional"))
      (node (ref "R57") (pin "PAD_1") (pinfunction "PIN1_PAD_1") (pintype "passive"))
    )
    (net (code "41") (name "/SR5_D1") (class "Default")
      (node (ref "IC5") (pin "1") (pinfunction "QB_1") (pintype "bidirectional"))
      (node (ref "R53") (pin "PAD_1") (pinfunction "PIN1_PAD_1") (pintype "passive"))
    )
    (net (code "42") (name "/SR5_D2") (class "Default")
      (node (ref "IC5") (pin "2") (pinfunction "QC_2") (pintype "bidirectional"))
      (node (ref "R33") (pin "PAD_1") (pinfunction "PIN1_PAD_1") (pintype "passive"))
    )
    (net (code "43") (name "/SR5_D3") (class "Default")
      (node (ref "IC5") (pin "3") (pinfunction "QD_3") (pintype "bidirectional"))
      (node (ref "R37") (pin "PAD_1") (pinfunction "PIN1_PAD_1") (pintype "passive"))
    )
    (net (code "44") (name "/SR5_D4") (class "Default")
      (node (ref "IC5") (pin "4") (pinfunction "QE_4") (pintype "bidirectional"))
      (node (ref "R61") (pin "PAD_1") (pinfunction "PIN1_PAD_1") (pintype "passive"))
    )
    (net (code "45") (name "/SR5_D5") (class "Default")
      (node (ref "IC5") (pin "5") (pinfunction "QF_5") (pintype "bidirectional"))
      (node (ref "R41") (pin "PAD_1") (pinfunction "PIN1_PAD_1") (pintype "passive"))
    )
    (net (code "46") (name "/SR5_D6") (class "Default")
      (node (ref "IC5") (pin "6") (pinfunction "QG_6") (pintype "bidirectional"))
      (node (ref "R49") (pin "PAD_1") (pinfunction "PIN1_PAD_1") (pintype "passive"))
    )
    (net (code "47") (name "/SR5_D7") (class "Default")
      (node (ref "IC5") (pin "7") (pinfunction "QH_7") (pintype "bidirectional"))
      (node (ref "R45") (pin "PAD_1") (pinfunction "PIN1_PAD_1") (pintype "passive"))
    )
    (net (code "48") (name "/SR6_D0") (class "Default")
      (node (ref "IC6") (pin "15") (pinfunction "QA_15") (pintype "bidirectional"))
      (node (ref "R58") (pin "PAD_1") (pinfunction "PIN1_PAD_1") (pintype "passive"))
    )
    (net (code "49") (name "/SR6_D1") (class "Default")
      (node (ref "IC6") (pin "1") (pinfunction "QB_1") (pintype "bidirectional"))
      (node (ref "R54") (pin "PAD_1") (pinfunction "PIN1_PAD_1") (pintype "passive"))
    )
    (net (code "50") (name "/SR6_D2") (class "Default")
      (node (ref "IC6") (pin "2") (pinfunction "QC_2") (pintype "bidirectional"))
      (node (ref "R34") (pin "PAD_1") (pinfunction "PIN1_PAD_1") (pintype "passive"))
    )
    (net (code "51") (name "/SR6_D3") (class "Default")
      (node (ref "IC6") (pin "3") (pinfunction "QD_3") (pintype "bidirectional"))
      (node (ref "R38") (pin "PAD_1") (pinfunction "PIN1_PAD_1") (pintype "passive"))
    )
    (net (code "52") (name "/SR6_D4") (class "Default")
      (node (ref "IC6") (pin "4") (pinfunction "QE_4") (pintype "bidirectional"))
      (node (ref "R62") (pin "PAD_1") (pinfunction "PIN1_PAD_1") (pintype "passive"))
    )
    (net (code "53") (name "/SR6_D5") (class "Default")
      (node (ref "IC6") (pin "5") (pinfunction "QF_5") (pintype "bidirectional"))
      (node (ref "R42") (pin "PAD_1") (pinfunction "PIN1_PAD_1") (pintype "passive"))
    )
    (net (code "54") (name "/SR6_D6") (class "Default")
      (node (ref "IC6") (pin "6") (pinfunction "QG_6") (pintype "bidirectional"))
      (node (ref "R50") (pin "PAD_1") (pinfunction "PIN1_PAD_1") (pintype "passive"))
    )
    (net (code "55") (name "/SR6_D7") (class "Default")
      (node (ref "IC6") (pin "7") (pinfunction "QH_7") (pintype "bidirectional"))
      (node (ref "R46") (pin "PAD_1") (pinfunction "PIN1_PAD_1") (pintype "passive"))
    )
    (net (code "56") (name "/SR7_D0") (class "Default")
      (node (ref "IC7") (pin "15") (pinfunction "QA_15") (pintype "bidirectional"))
      (node (ref "R59") (pin "PAD_1") (pinfunction "PIN1_PAD_1") (pintype "passive"))
    )
    (net (code "57") (name "/SR7_D1") (class "Default")
      (node (ref "IC7") (pin "1") (pinfunction "QB_1") (pintype "bidirectional"))
      (node (ref "R55") (pin "PAD_1") (pinfunction "PIN1_PAD_1") (pintype "passive"))
    )
    (net (code "58") (name "/SR7_D2") (class "Default")
      (node (ref "IC7") (pin "2") (pinfunction "QC_2") (pintype "bidirectional"))
      (node (ref "R35") (pin "PAD_1") (pinfunction "PIN1_PAD_1") (pintype "passive"))
    )
    (net (code "59") (name "/SR7_D3") (class "Default")
      (node (ref "IC7") (pin "3") (pinfunction "QD_3") (pintype "bidirectional"))
      (node (ref "R39") (pin "PAD_1") (pinfunction "PIN1_PAD_1") (pintype "passive"))
    )
    (net (code "60") (name "/SR7_D4") (class "Default")
      (node (ref "IC7") (pin "4") (pinfunction "QE_4") (pintype "bidirectional"))
      (node (ref "R63") (pin "PAD_1") (pinfunction "PIN1_PAD_1") (pintype "passive"))
    )
    (net (code "61") (name "/SR7_D5") (class "Default")
      (node (ref "IC7") (pin "5") (pinfunction "QF_5") (pintype "bidirectional"))
      (node (ref "R43") (pin "PAD_1") (pinfunction "PIN1_PAD_1") (pintype "passive"))
    )
    (net (code "62") (name "/SR7_D6") (class "Default")
      (node (ref "IC7") (pin "6") (pinfunction "QG_6") (pintype "bidirectional"))
      (node (ref "R51") (pin "PAD_1") (pinfunction "PIN1_PAD_1") (pintype "passive"))
    )
    (net (code "63") (name "/SR7_D7") (class "Default")
      (node (ref "IC7") (pin "7") (pinfunction "QH_7") (pintype "bidirectional"))
      (node (ref "R47") (pin "PAD_1") (pinfunction "PIN1_PAD_1") (pintype "passive"))
    )
    (net (code "64") (name "/SR8_D0") (class "Default")
      (node (ref "IC8") (pin "15") (pinfunction "QA_15") (pintype "bidirectional"))
      (node (ref "R60") (pin "PAD_1") (pinfunction "PIN1_PAD_1") (pintype "passive"))
    )
    (net (code "65") (name "/SR8_D1") (class "Default")
      (node (ref "IC8") (pin "1") (pinfunction "QB_1") (pintype "bidirectional"))
      (node (ref "R56") (pin "PAD_1") (pinfunction "PIN1_PAD_1") (pintype "passive"))
    )
    (net (code "66") (name "/SR8_D2") (class "Default")
      (node (ref "IC8") (pin "2") (pinfunction "QC_2") (pintype "bidirectional"))
      (node (ref "R36") (pin "PAD_1") (pinfunction "PIN1_PAD_1") (pintype "passive"))
    )
    (net (code "67") (name "/SR8_D3") (class "Default")
      (node (ref "IC8") (pin "3") (pinfunction "QD_3") (pintype "bidirectional"))
      (node (ref "R40") (pin "PAD_1") (pinfunction "PIN1_PAD_1") (pintype "passive"))
    )
    (net (code "68") (name "/SR8_D4") (class "Default")
      (node (ref "IC8") (pin "4") (pinfunction "QE_4") (pintype "bidirectional"))
      (node (ref "R64") (pin "PAD_1") (pinfunction "PIN1_PAD_1") (pintype "passive"))
    )
    (net (code "69") (name "/SR8_D5") (class "Default")
      (node (ref "IC8") (pin "5") (pinfunction "QF_5") (pintype "bidirectional"))
      (node (ref "R44") (pin "PAD_1") (pinfunction "PIN1_PAD_1") (pintype "passive"))
    )
    (net (code "70") (name "/SR8_D6") (class "Default")
      (node (ref "IC8") (pin "6") (pinfunction "QG_6") (pintype "bidirectional"))
      (node (ref "R52") (pin "PAD_1") (pinfunction "PIN1_PAD_1") (pintype "passive"))
    )
    (net (code "71") (name "/SR8_D7") (class "Default")
      (node (ref "IC8") (pin "7") (pinfunction "QH_7") (pintype "bidirectional"))
      (node (ref "R48") (pin "PAD_1") (pinfunction "PIN1_PAD_1") (pintype "passive"))
    )
    (net (code "72") (name "/SR9_D0") (class "Default")
      (node (ref "IC12") (pin "15") (pinfunction "QA_15") (pintype "bidirectional"))
      (node (ref "R93") (pin "PAD_1") (pinfunction "PIN1_PAD_1") (pintype "passive"))
    )
    (net (code "73") (name "/SR9_D1") (class "Default")
      (node (ref "IC12") (pin "1") (pinfunction "QB_1") (pintype "bidirectional"))
      (node (ref "R73") (pin "PAD_1") (pinfunction "PIN1_PAD_1") (pintype "passive"))
    )
    (net (code "74") (name "/SR9_D2") (class "Default")
      (node (ref "IC12") (pin "2") (pinfunction "QC_2") (pintype "bidirectional"))
      (node (ref "R77") (pin "PAD_1") (pinfunction "PIN1_PAD_1") (pintype "passive"))
    )
    (net (code "75") (name "/SR9_D3") (class "Default")
      (node (ref "IC12") (pin "3") (pinfunction "QD_3") (pintype "bidirectional"))
      (node (ref "R81") (pin "PAD_1") (pinfunction "PIN1_PAD_1") (pintype "passive"))
    )
    (net (code "76") (name "/SR9_D4") (class "Default")
      (node (ref "IC12") (pin "4") (pinfunction "QE_4") (pintype "bidirectional"))
      (node (ref "R89") (pin "PAD_1") (pinfunction "PIN1_PAD_1") (pintype "passive"))
    )
    (net (code "77") (name "/SR9_D5") (class "Default")
      (node (ref "IC12") (pin "5") (pinfunction "QF_5") (pintype "bidirectional"))
      (node (ref "R85") (pin "PAD_1") (pinfunction "PIN1_PAD_1") (pintype "passive"))
    )
    (net (code "78") (name "/SR9_D6") (class "Default")
      (node (ref "IC12") (pin "6") (pinfunction "QG_6") (pintype "bidirectional"))
      (node (ref "R69") (pin "PAD_1") (pinfunction "PIN1_PAD_1") (pintype "passive"))
    )
    (net (code "79") (name "/SR9_D7") (class "Default")
      (node (ref "IC12") (pin "7") (pinfunction "QH_7") (pintype "bidirectional"))
      (node (ref "R65") (pin "PAD_1") (pinfunction "PIN1_PAD_1") (pintype "passive"))
    )
    (net (code "80") (name "/SR10_D0") (class "Default")
      (node (ref "IC11") (pin "15") (pinfunction "QA_15") (pintype "bidirectional"))
      (node (ref "R94") (pin "PAD_1") (pinfunction "PIN1_PAD_1") (pintype "passive"))
    )
    (net (code "81") (name "/SR10_D1") (class "Default")
      (node (ref "IC11") (pin "1") (pinfunction "QB_1") (pintype "bidirectional"))
      (node (ref "R74") (pin "PAD_1") (pinfunction "PIN1_PAD_1") (pintype "passive"))
    )
    (net (code "82") (name "/SR10_D2") (class "Default")
      (node (ref "IC11") (pin "2") (pinfunction "QC_2") (pintype "bidirectional"))
      (node (ref "R78") (pin "PAD_1") (pinfunction "PIN1_PAD_1") (pintype "passive"))
    )
    (net (code "83") (name "/SR10_D3") (class "Default")
      (node (ref "IC11") (pin "3") (pinfunction "QD_3") (pintype "bidirectional"))
      (node (ref "R82") (pin "PAD_1") (pinfunction "PIN1_PAD_1") (pintype "passive"))
    )
    (net (code "84") (name "/SR10_D4") (class "Default")
      (node (ref "IC11") (pin "4") (pinfunction "QE_4") (pintype "bidirectional"))
      (node (ref "R90") (pin "PAD_1") (pinfunction "PIN1_PAD_1") (pintype "passive"))
    )
    (net (code "85") (name "/SR10_D5") (class "Default")
      (node (ref "IC11") (pin "5") (pinfunction "QF_5") (pintype "bidirectional"))
      (node (ref "R86") (pin "PAD_1") (pinfunction "PIN1_PAD_1") (pintype "passive"))
    )
    (net (code "86") (name "/SR10_D6") (class "Default")
      (node (ref "IC11") (pin "6") (pinfunction "QG_6") (pintype "bidirectional"))
      (node (ref "R70") (pin "PAD_1") (pinfunction "PIN1_PAD_1") (pintype "passive"))
    )
    (net (code "87") (name "/SR10_D7") (class "Default")
      (node (ref "IC11") (pin "7") (pinfunction "QH_7") (pintype "bidirectional"))
      (node (ref "R66") (pin "PAD_1") (pinfunction "PIN1_PAD_1") (pintype "passive"))
    )
    (net (code "88") (name "/SR11_D0") (class "Default")
      (node (ref "IC10") (pin "15") (pinfunction "QA_15") (pintype "bidirectional"))
      (node (ref "R95") (pin "PAD_1") (pinfunction "PIN1_PAD_1") (pintype "passive"))
    )
    (net (code "89") (name "/SR11_D1") (class "Default")
      (node (ref "IC10") (pin "1") (pinfunction "QB_1") (pintype "bidirectional"))
      (node (ref "R75") (pin "PAD_1") (pinfunction "PIN1_PAD_1") (pintype "passive"))
    )
    (net (code "90") (name "/SR11_D2") (class "Default")
      (node (ref "IC10") (pin "2") (pinfunction "QC_2") (pintype "bidirectional"))
      (node (ref "R79") (pin "PAD_1") (pinfunction "PIN1_PAD_1") (pintype "passive"))
    )
    (net (code "91") (name "/SR11_D3") (class "Default")
      (node (ref "IC10") (pin "3") (pinfunction "QD_3") (pintype "bidirectional"))
      (node (ref "R83") (pin "PAD_1") (pinfunction "PIN1_PAD_1") (pintype "passive"))
    )
    (net (code "92") (name "/SR11_D4") (class "Default")
      (node (ref "IC10") (pin "4") (pinfunction "QE_4") (pintype "bidirectional"))
      (node (ref "R91") (pin "PAD_1") (pinfunction "PIN1_PAD_1") (pintype "passive"))
    )
    (net (code "93") (name "/SR11_D5") (class "Default")
      (node (ref "IC10") (pin "5") (pinfunction "QF_5") (pintype "bidirectional"))
      (node (ref "R87") (pin "PAD_1") (pinfunction "PIN1_PAD_1") (pintype "passive"))
    )
    (net (code "94") (name "/SR11_D6") (class "Default")
      (node (ref "IC10") (pin "6") (pinfunction "QG_6") (pintype "bidirectional"))
      (node (ref "R71") (pin "PAD_1") (pinfunction "PIN1_PAD_1") (pintype "passive"))
    )
    (net (code "95") (name "/SR11_D7") (class "Default")
      (node (ref "IC10") (pin "7") (pinfunction "QH_7") (pintype "bidirectional"))
      (node (ref "R67") (pin "PAD_1") (pinfunction "PIN1_PAD_1") (pintype "passive"))
    )
    (net (code "96") (name "/SR12_D0") (class "Default")
      (node (ref "IC9") (pin "15") (pinfunction "QA_15") (pintype "bidirectional"))
      (node (ref "R96") (pin "PAD_1") (pinfunction "PIN1_PAD_1") (pintype "passive"))
    )
    (net (code "97") (name "/SR12_D1") (class "Default")
      (node (ref "IC9") (pin "1") (pinfunction "QB_1") (pintype "bidirectional"))
      (node (ref "R76") (pin "PAD_1") (pinfunction "PIN1_PAD_1") (pintype "passive"))
    )
    (net (code "98") (name "/SR12_D2") (class "Default")
      (node (ref "IC9") (pin "2") (pinfunction "QC_2") (pintype "bidirectional"))
      (node (ref "R80") (pin "PAD_1") (pinfunction "PIN1_PAD_1") (pintype "passive"))
    )
    (net (code "99") (name "/SR12_D3") (class "Default")
      (node (ref "IC9") (pin "3") (pinfunction "QD_3") (pintype "bidirectional"))
      (node (ref "R84") (pin "PAD_1") (pinfunction "PIN1_PAD_1") (pintype "passive"))
    )
    (net (code "100") (name "/SR12_D4") (class "Default")
      (node (ref "IC9") (pin "4") (pinfunction "QE_4") (pintype "bidirectional"))
      (node (ref "R92") (pin "PAD_1") (pinfunction "PIN1_PAD_1") (pintype "passive"))
    )
    (net (code "101") (name "/SR12_D5") (class "Default")
      (node (ref "IC9") (pin "5") (pinfunction "QF_5") (pintype "bidirectional"))
      (node (ref "R88") (pin "PAD_1") (pinfunction "PIN1_PAD_1") (pintype "passive"))
    )
    (net (code "102") (name "/SR12_D6") (class "Default")
      (node (ref "IC9") (pin "6") (pinfunction "QG_6") (pintype "bidirectional"))
      (node (ref "R72") (pin "PAD_1") (pinfunction "PIN1_PAD_1") (pintype "passive"))
    )
    (net (code "103") (name "/SR12_D7") (class "Default")
      (node (ref "IC9") (pin "7") (pinfunction "QH_7") (pintype "bidirectional"))
      (node (ref "R68") (pin "PAD_1") (pinfunction "PIN1_PAD_1") (pintype "passive"))
    )
    (net (code "104") (name "GND") (class "Default")
      (node (ref "C1") (pin "PAD_0") (pinfunction "PIN0_PAD_0") (pintype "bidirectional"))
      (node (ref "C10") (pin "PAD_0") (pinfunction "PIN0_PAD_0") (pintype "bidirectional"))
      (node (ref "C11") (pin "PAD_0") (pinfunction "PIN0_PAD_0") (pintype "bidirectional"))
      (node (ref "C12") (pin "PAD_0") (pinfunction "PIN0_PAD_0") (pintype "bidirectional"))
      (node (ref "C13") (pin "MINUS") (pinfunction "MINUS_MINUS") (pintype "bidirectional"))
      (node (ref "C2") (pin "PAD_0") (pinfunction "PIN0_PAD_0") (pintype "bidirectional"))
      (node (ref "C3") (pin "PAD_0") (pinfunction "PIN0_PAD_0") (pintype "bidirectional"))
      (node (ref "C4") (pin "PAD_0") (pinfunction "PIN0_PAD_0") (pintype "bidirectional"))
      (node (ref "C5") (pin "PAD_0") (pinfunction "PIN0_PAD_0") (pintype "bidirectional"))
      (node (ref "C6") (pin "PAD_0") (pinfunction "PIN0_PAD_0") (pintype "bidirectional"))
      (node (ref "C7") (pin "PAD_0") (pinfunction "PIN0_PAD_0") (pintype "bidirectional"))
      (node (ref "C8") (pin "PAD_0") (pinfunction "PIN0_PAD_0") (pintype "bidirectional"))
      (node (ref "C9") (pin "PAD_0") (pinfunction "PIN0_PAD_0") (pintype "bidirectional"))
      (node (ref "D1") (pin "ANODE") (pinfunction "ANODE_ANODE") (pintype "passive"))
      (node (ref "DS1") (pin "3") (pinfunction "COM_3") (pintype "passive"))
      (node (ref "DS1") (pin "8") (pinfunction "COM_8") (pintype "passive"))
      (node (ref "DS10") (pin "3") (pinfunction "COM_3") (pintype "passive"))
      (node (ref "DS10") (pin "8") (pinfunction "COM_8") (pintype "passive"))
      (node (ref "DS11") (pin "3") (pinfunction "COM_3") (pintype "passive"))
      (node (ref "DS11") (pin "8") (pinfunction "COM_8") (pintype "passive"))
      (node (ref "DS12") (pin "3") (pinfunction "COM_3") (pintype "passive"))
      (node (ref "DS12") (pin "8") (pinfunction "COM_8") (pintype "passive"))
      (node (ref "DS2") (pin "3") (pinfunction "COM_3") (pintype "passive"))
      (node (ref "DS2") (pin "8") (pinfunction "COM_8") (pintype "passive"))
      (node (ref "DS3") (pin "3") (pinfunction "COM_3") (pintype "passive"))
      (node (ref "DS3") (pin "8") (pinfunction "COM_8") (pintype "passive"))
      (node (ref "DS4") (pin "3") (pinfunction "COM_3") (pintype "passive"))
      (node (ref "DS4") (pin "8") (pinfunction "COM_8") (pintype "passive"))
      (node (ref "DS5") (pin "3") (pinfunction "COM_3") (pintype "passive"))
      (node (ref "DS5") (pin "8") (pinfunction "COM_8") (pintype "passive"))
      (node (ref "DS6") (pin "3") (pinfunction "COM_3") (pintype "passive"))
      (node (ref "DS6") (pin "8") (pinfunction "COM_8") (pintype "passive"))
      (node (ref "DS7") (pin "3") (pinfunction "COM_3") (pintype "passive"))
      (node (ref "DS7") (pin "8") (pinfunction "COM_8") (pintype "passive"))
      (node (ref "DS8") (pin "3") (pinfunction "COM_3") (pintype "passive"))
      (node (ref "DS8") (pin "8") (pinfunction "COM_8") (pintype "passive"))
      (node (ref "DS9") (pin "3") (pinfunction "COM_3") (pintype "passive"))
      (node (ref "DS9") (pin "8") (pinfunction "COM_8") (pintype "passive"))
      (node (ref "IC1") (pin "13") (pinfunction "~{OE}_13") (pintype "bidirectional"))
      (node (ref "IC1") (pin "8") (pinfunction "GND_8") (pintype "bidirectional"))
      (node (ref "IC10") (pin "13") (pinfunction "~{OE}_13") (pintype "bidirectional"))
      (node (ref "IC10") (pin "8") (pinfunction "GND_8") (pintype "bidirectional"))
      (node (ref "IC11") (pin "13") (pinfunction "~{OE}_13") (pintype "bidirectional"))
      (node (ref "IC11") (pin "8") (pinfunction "GND_8") (pintype "bidirectional"))
      (node (ref "IC12") (pin "13") (pinfunction "~{OE}_13") (pintype "bidirectional"))
      (node (ref "IC12") (pin "8") (pinfunction "GND_8") (pintype "bidirectional"))
      (node (ref "IC2") (pin "13") (pinfunction "~{OE}_13") (pintype "bidirectional"))
      (node (ref "IC2") (pin "8") (pinfunction "GND_8") (pintype "bidirectional"))
      (node (ref "IC3") (pin "13") (pinfunction "~{OE}_13") (pintype "bidirectional"))
      (node (ref "IC3") (pin "8") (pinfunction "GND_8") (pintype "bidirectional"))
      (node (ref "IC4") (pin "13") (pinfunction "~{OE}_13") (pintype "bidirectional"))
      (node (ref "IC4") (pin "8") (pinfunction "GND_8") (pintype "bidirectional"))
      (node (ref "IC5") (pin "13") (pinfunction "~{OE}_13") (pintype "bidirectional"))
      (node (ref "IC5") (pin "8") (pinfunction "GND_8") (pintype "bidirectional"))
      (node (ref "IC6") (pin "13") (pinfunction "~{OE}_13") (pintype "bidirectional"))
      (node (ref "IC6") (pin "8") (pinfunction "GND_8") (pintype "bidirectional"))
      (node (ref "IC7") (pin "13") (pinfunction "~{OE}_13") (pintype "bidirectional"))
      (node (ref "IC7") (pin "8") (pinfunction "GND_8") (pintype "bidirectional"))
      (node (ref "IC8") (pin "13") (pinfunction "~{OE}_13") (pintype "bidirectional"))
      (node (ref "IC8") (pin "8") (pinfunction "GND_8") (pintype "bidirectional"))
      (node (ref "IC9") (pin "13") (pinfunction "~{OE}_13") (pintype "bidirectional"))
      (node (ref "IC9") (pin "8") (pinfunction "GND_8") (pintype "bidirectional"))
      (node (ref "KEY1") (pin "3") (pinfunction "2_3") (pintype "bidirectional"))
      (node (ref "KEY1") (pin "4") (pinfunction "2_4") (pintype "bidirectional"))
      (node (ref "KEY2") (pin "3") (pinfunction "2_3") (pintype "bidirectional"))
      (node (ref "KEY2") (pin "4") (pinfunction "2_4") (pintype "bidirectional"))
      (node (ref "KEY3") (pin "3") (pinfunction "2_3") (pintype "bidirectional"))
      (node (ref "KEY3") (pin "4") (pinfunction "2_4") (pintype "bidirectional"))
      (node (ref "X1") (pin "5") (pinfunction "5_5") (pintype "passive"))
      (node (ref "X1_1") (pin "5") (pinfunction "5_5") (pintype "passive"))
    )
    (net (code "105") (name "Net-(DS1-A)") (class "Default")
      (node (ref "DS1") (pin "7") (pinfunction "A_7") (pintype "passive"))
      (node (ref "R1") (pin "PAD_0") (pinfunction "PIN0_PAD_0") (pintype "passive"))
    )
    (net (code "106") (name "Net-(DS1-B)") (class "Default")
      (node (ref "DS1") (pin "6") (pinfunction "B_6") (pintype "passive"))
      (node (ref "R5") (pin "PAD_0") (pinfunction "PIN0_PAD_0") (pintype "passive"))
    )
    (net (code "107") (name "Net-(DS1-C)") (class "Default")
      (node (ref "DS1") (pin "4") (pinfunction "C_4") (pintype "passive"))
      (node (ref "R9") (pin "PAD_0") (pinfunction "PIN0_PAD_0") (pintype "passive"))
    )
    (net (code "108") (name "Net-(DS1-D)") (class "Default")
      (node (ref "DS1") (pin "2") (pinfunction "D_2") (pintype "passive"))
      (node (ref "R13") (pin "PAD_0") (pinfunction "PIN0_PAD_0") (pintype "passive"))
    )
    (net (code "109") (name "Net-(DS1-DOT)") (class "Default")
      (node (ref "DS1") (pin "5") (pinfunction "DOT_5") (pintype "passive"))
      (node (ref "R29") (pin "PAD_0") (pinfunction "PIN0_PAD_0") (pintype "passive"))
    )
    (net (code "110") (name "Net-(DS1-E)") (class "Default")
      (node (ref "DS1") (pin "1") (pinfunction "E_1") (pintype "passive"))
      (node (ref "R17") (pin "PAD_0") (pinfunction "PIN0_PAD_0") (pintype "passive"))
    )
    (net (code "111") (name "Net-(DS1-F)") (class "Default")
      (node (ref "DS1") (pin "9") (pinfunction "F_9") (pintype "passive"))
      (node (ref "R21") (pin "PAD_0") (pinfunction "PIN0_PAD_0") (pintype "passive"))
    )
    (net (code "112") (name "Net-(DS1-G)") (class "Default")
      (node (ref "DS1") (pin "10") (pinfunction "G_10") (pintype "passive"))
      (node (ref "R25") (pin "PAD_0") (pinfunction "PIN0_PAD_0") (pintype "passive"))
    )
    (net (code "113") (name "Net-(DS2-A)") (class "Default")
      (node (ref "DS2") (pin "7") (pinfunction "A_7") (pintype "passive"))
      (node (ref "R2") (pin "PAD_0") (pinfunction "PIN0_PAD_0") (pintype "passive"))
    )
    (net (code "114") (name "Net-(DS2-B)") (class "Default")
      (node (ref "DS2") (pin "6") (pinfunction "B_6") (pintype "passive"))
      (node (ref "R6") (pin "PAD_0") (pinfunction "PIN0_PAD_0") (pintype "passive"))
    )
    (net (code "115") (name "Net-(DS2-C)") (class "Default")
      (node (ref "DS2") (pin "4") (pinfunction "C_4") (pintype "passive"))
      (node (ref "R10") (pin "PAD_0") (pinfunction "PIN0_PAD_0") (pintype "passive"))
    )
    (net (code "116") (name "Net-(DS2-D)") (class "Default")
      (node (ref "DS2") (pin "2") (pinfunction "D_2") (pintype "passive"))
      (node (ref "R14") (pin "PAD_0") (pinfunction "PIN0_PAD_0") (pintype "passive"))
    )
    (net (code "117") (name "Net-(DS2-DOT)") (class "Default")
      (node (ref "DS2") (pin "5") (pinfunction "DOT_5") (pintype "passive"))
      (node (ref "R30") (pin "PAD_0") (pinfunction "PIN0_PAD_0") (pintype "passive"))
    )
    (net (code "118") (name "Net-(DS2-E)") (class "Default")
      (node (ref "DS2") (pin "1") (pinfunction "E_1") (pintype "passive"))
      (node (ref "R18") (pin "PAD_0") (pinfunction "PIN0_PAD_0") (pintype "passive"))
    )
    (net (code "119") (name "Net-(DS2-F)") (class "Default")
      (node (ref "DS2") (pin "9") (pinfunction "F_9") (pintype "passive"))
      (node (ref "R22") (pin "PAD_0") (pinfunction "PIN0_PAD_0") (pintype "passive"))
    )
    (net (code "120") (name "Net-(DS2-G)") (class "Default")
      (node (ref "DS2") (pin "10") (pinfunction "G_10") (pintype "passive"))
      (node (ref "R26") (pin "PAD_0") (pinfunction "PIN0_PAD_0") (pintype "passive"))
    )
    (net (code "121") (name "Net-(DS3-A)") (class "Default")
      (node (ref "DS3") (pin "7") (pinfunction "A_7") (pintype "passive"))
      (node (ref "R3") (pin "PAD_0") (pinfunction "PIN0_PAD_0") (pintype "passive"))
    )
    (net (code "122") (name "Net-(DS3-B)") (class "Default")
      (node (ref "DS3") (pin "6") (pinfunction "B_6") (pintype "passive"))
      (node (ref "R7") (pin "PAD_0") (pinfunction "PIN0_PAD_0") (pintype "passive"))
    )
    (net (code "123") (name "Net-(DS3-C)") (class "Default")
      (node (ref "DS3") (pin "4") (pinfunction "C_4") (pintype "passive"))
      (node (ref "R11") (pin "PAD_0") (pinfunction "PIN0_PAD_0") (pintype "passive"))
    )
    (net (code "124") (name "Net-(DS3-D)") (class "Default")
      (node (ref "DS3") (pin "2") (pinfunction "D_2") (pintype "passive"))
      (node (ref "R15") (pin "PAD_0") (pinfunction "PIN0_PAD_0") (pintype "passive"))
    )
    (net (code "125") (name "Net-(DS3-DOT)") (class "Default")
      (node (ref "DS3") (pin "5") (pinfunction "DOT_5") (pintype "passive"))
      (node (ref "R31") (pin "PAD_0") (pinfunction "PIN0_PAD_0") (pintype "passive"))
    )
    (net (code "126") (name "Net-(DS3-E)") (class "Default")
      (node (ref "DS3") (pin "1") (pinfunction "E_1") (pintype "passive"))
      (node (ref "R19") (pin "PAD_0") (pinfunction "PIN0_PAD_0") (pintype "passive"))
    )
    (net (code "127") (name "Net-(DS3-F)") (class "Default")
      (node (ref "DS3") (pin "9") (pinfunction "F_9") (pintype "passive"))
      (node (ref "R23") (pin "PAD_0") (pinfunction "PIN0_PAD_0") (pintype "passive"))
    )
    (net (code "128") (name "Net-(DS3-G)") (class "Default")
      (node (ref "DS3") (pin "10") (pinfunction "G_10") (pintype "passive"))
      (node (ref "R27") (pin "PAD_0") (pinfunction "PIN0_PAD_0") (pintype "passive"))
    )
    (net (code "129") (name "Net-(DS4-A)") (class "Default")
      (node (ref "DS4") (pin "7") (pinfunction "A_7") (pintype "passive"))
      (node (ref "R4") (pin "PAD_0") (pinfunction "PIN0_PAD_0") (pintype "passive"))
    )
    (net (code "130") (name "Net-(DS4-B)") (class "Default")
      (node (ref "DS4") (pin "6") (pinfunction "B_6") (pintype "passive"))
      (node (ref "R8") (pin "PAD_0") (pinfunction "PIN0_PAD_0") (pintype "passive"))
    )
    (net (code "131") (name "Net-(DS4-C)") (class "Default")
      (node (ref "DS4") (pin "4") (pinfunction "C_4") (pintype "passive"))
      (node (ref "R12") (pin "PAD_0") (pinfunction "PIN0_PAD_0") (pintype "passive"))
    )
    (net (code "132") (name "Net-(DS4-D)") (class "Default")
      (node (ref "DS4") (pin "2") (pinfunction "D_2") (pintype "passive"))
      (node (ref "R16") (pin "PAD_0") (pinfunction "PIN0_PAD_0") (pintype "passive"))
    )
    (net (code "133") (name "Net-(DS4-DOT)") (class "Default")
      (node (ref "DS4") (pin "5") (pinfunction "DOT_5") (pintype "passive"))
      (node (ref "R32") (pin "PAD_0") (pinfunction "PIN0_PAD_0") (pintype "passive"))
    )
    (net (code "134") (name "Net-(DS4-E)") (class "Default")
      (node (ref "DS4") (pin "1") (pinfunction "E_1") (pintype "passive"))
      (node (ref "R20") (pin "PAD_0") (pinfunction "PIN0_PAD_0") (pintype "passive"))
    )
    (net (code "135") (name "Net-(DS4-F)") (class "Default")
      (node (ref "DS4") (pin "9") (pinfunction "F_9") (pintype "passive"))
      (node (ref "R24") (pin "PAD_0") (pinfunction "PIN0_PAD_0") (pintype "passive"))
    )
    (net (code "136") (name "Net-(DS4-G)") (class "Default")
      (node (ref "DS4") (pin "10") (pinfunction "G_10") (pintype "passive"))
      (node (ref "R28") (pin "PAD_0") (pinfunction "PIN0_PAD_0") (pintype "passive"))
    )
    (net (code "137") (name "Net-(DS5-A)") (class "Default")
      (node (ref "DS5") (pin "7") (pinfunction "A_7") (pintype "passive"))
      (node (ref "R33") (pin "PAD_0") (pinfunction "PIN0_PAD_0") (pintype "passive"))
    )
    (net (code "138") (name "Net-(DS5-B)") (class "Default")
      (node (ref "DS5") (pin "6") (pinfunction "B_6") (pintype "passive"))
      (node (ref "R37") (pin "PAD_0") (pinfunction "PIN0_PAD_0") (pintype "passive"))
    )
    (net (code "139") (name "Net-(DS5-C)") (class "Default")
      (node (ref "DS5") (pin "4") (pinfunction "C_4") (pintype "passive"))
      (node (ref "R41") (pin "PAD_0") (pinfunction "PIN0_PAD_0") (pintype "passive"))
    )
    (net (code "140") (name "Net-(DS5-D)") (class "Default")
      (node (ref "DS5") (pin "2") (pinfunction "D_2") (pintype "passive"))
      (node (ref "R45") (pin "PAD_0") (pinfunction "PIN0_PAD_0") (pintype "passive"))
    )
    (net (code "141") (name "Net-(DS5-DOT)") (class "Default")
      (node (ref "DS5") (pin "5") (pinfunction "DOT_5") (pintype "passive"))
      (node (ref "R61") (pin "PAD_0") (pinfunction "PIN0_PAD_0") (pintype "passive"))
    )
    (net (code "142") (name "Net-(DS5-E)") (class "Default")
      (node (ref "DS5") (pin "1") (pinfunction "E_1") (pintype "passive"))
      (node (ref "R49") (pin "PAD_0") (pinfunction "PIN0_PAD_0") (pintype "passive"))
    )
    (net (code "143") (name "Net-(DS5-F)") (class "Default")
      (node (ref "DS5") (pin "9") (pinfunction "F_9") (pintype "passive"))
      (node (ref "R53") (pin "PAD_0") (pinfunction "PIN0_PAD_0") (pintype "passive"))
    )
    (net (code "144") (name "Net-(DS5-G)") (class "Default")
      (node (ref "DS5") (pin "10") (pinfunction "G_10") (pintype "passive"))
      (node (ref "R57") (pin "PAD_0") (pinfunction "PIN0_PAD_0") (pintype "passive"))
    )
    (net (code "145") (name "Net-(DS6-A)") (class "Default")
      (node (ref "DS6") (pin "7") (pinfunction "A_7") (pintype "passive"))
      (node (ref "R34") (pin "PAD_0") (pinfunction "PIN0_PAD_0") (pintype "passive"))
    )
    (net (code "146") (name "Net-(DS6-B)") (class "Default")
      (node (ref "DS6") (pin "6") (pinfunction "B_6") (pintype "passive"))
      (node (ref "R38") (pin "PAD_0") (pinfunction "PIN0_PAD_0") (pintype "passive"))
    )
    (net (code "147") (name "Net-(DS6-C)") (class "Default")
      (node (ref "DS6") (pin "4") (pinfunction "C_4") (pintype "passive"))
      (node (ref "R42") (pin "PAD_0") (pinfunction "PIN0_PAD_0") (pintype "passive"))
    )
    (net (code "148") (name "Net-(DS6-D)") (class "Default")
      (node (ref "DS6") (pin "2") (pinfunction "D_2") (pintype "passive"))
      (node (ref "R46") (pin "PAD_0") (pinfunction "PIN0_PAD_0") (pintype "passive"))
    )
    (net (code "149") (name "Net-(DS6-DOT)") (class "Default")
      (node (ref "DS6") (pin "5") (pinfunction "DOT_5") (pintype "passive"))
      (node (ref "R62") (pin "PAD_0") (pinfunction "PIN0_PAD_0") (pintype "passive"))
    )
    (net (code "150") (name "Net-(DS6-E)") (class "Default")
      (node (ref "DS6") (pin "1") (pinfunction "E_1") (pintype "passive"))
      (node (ref "R50") (pin "PAD_0") (pinfunction "PIN0_PAD_0") (pintype "passive"))
    )
    (net (code "151") (name "Net-(DS6-F)") (class "Default")
      (node (ref "DS6") (pin "9") (pinfunction "F_9") (pintype "passive"))
      (node (ref "R54") (pin "PAD_0") (pinfunction "PIN0_PAD_0") (pintype "passive"))
    )
    (net (code "152") (name "Net-(DS6-G)") (class "Default")
      (node (ref "DS6") (pin "10") (pinfunction "G_10") (pintype "passive"))
      (node (ref "R58") (pin "PAD_0") (pinfunction "PIN0_PAD_0") (pintype "passive"))
    )
    (net (code "153") (name "Net-(DS7-A)") (class "Default")
      (node (ref "DS7") (pin "7") (pinfunction "A_7") (pintype "passive"))
      (node (ref "R35") (pin "PAD_0") (pinfunction "PIN0_PAD_0") (pintype "passive"))
    )
    (net (code "154") (name "Net-(DS7-B)") (class "Default")
      (node (ref "DS7") (pin "6") (pinfunction "B_6") (pintype "passive"))
      (node (ref "R39") (pin "PAD_0") (pinfunction "PIN0_PAD_0") (pintype "passive"))
    )
    (net (code "155") (name "Net-(DS7-C)") (class "Default")
      (node (ref "DS7") (pin "4") (pinfunction "C_4") (pintype "passive"))
      (node (ref "R43") (pin "PAD_0") (pinfunction "PIN0_PAD_0") (pintype "passive"))
    )
    (net (code "156") (name "Net-(DS7-D)") (class "Default")
      (node (ref "DS7") (pin "2") (pinfunction "D_2") (pintype "passive"))
      (node (ref "R47") (pin "PAD_0") (pinfunction "PIN0_PAD_0") (pintype "passive"))
    )
    (net (code "157") (name "Net-(DS7-DOT)") (class "Default")
      (node (ref "DS7") (pin "5") (pinfunction "DOT_5") (pintype "passive"))
      (node (ref "R63") (pin "PAD_0") (pinfunction "PIN0_PAD_0") (pintype "passive"))
    )
    (net (code "158") (name "Net-(DS7-E)") (class "Default")
      (node (ref "DS7") (pin "1") (pinfunction "E_1") (pintype "passive"))
      (node (ref "R51") (pin "PAD_0") (pinfunction "PIN0_PAD_0") (pintype "passive"))
    )
    (net (code "159") (name "Net-(DS7-F)") (class "Default")
      (node (ref "DS7") (pin "9") (pinfunction "F_9") (pintype "passive"))
      (node (ref "R55") (pin "PAD_0") (pinfunction "PIN0_PAD_0") (pintype "passive"))
    )
    (net (code "160") (name "Net-(DS7-G)") (class "Default")
      (node (ref "DS7") (pin "10") (pinfunction "G_10") (pintype "passive"))
      (node (ref "R59") (pin "PAD_0") (pinfunction "PIN0_PAD_0") (pintype "passive"))
    )
    (net (code "161") (name "Net-(DS8-A)") (class "Default")
      (node (ref "DS8") (pin "7") (pinfunction "A_7") (pintype "passive"))
      (node (ref "R36") (pin "PAD_0") (pinfunction "PIN0_PAD_0") (pintype "passive"))
    )
    (net (code "162") (name "Net-(DS8-B)") (class "Default")
      (node (ref "DS8") (pin "6") (pinfunction "B_6") (pintype "passive"))
      (node (ref "R40") (pin "PAD_0") (pinfunction "PIN0_PAD_0") (pintype "passive"))
    )
    (net (code "163") (name "Net-(DS8-C)") (class "Default")
      (node (ref "DS8") (pin "4") (pinfunction "C_4") (pintype "passive"))
      (node (ref "R44") (pin "PAD_0") (pinfunction "PIN0_PAD_0") (pintype "passive"))
    )
    (net (code "164") (name "Net-(DS8-D)") (class "Default")
      (node (ref "DS8") (pin "2") (pinfunction "D_2") (pintype "passive"))
      (node (ref "R48") (pin "PAD_0") (pinfunction "PIN0_PAD_0") (pintype "passive"))
    )
    (net (code "165") (name "Net-(DS8-DOT)") (class "Default")
      (node (ref "DS8") (pin "5") (pinfunction "DOT_5") (pintype "passive"))
      (node (ref "R64") (pin "PAD_0") (pinfunction "PIN0_PAD_0") (pintype "passive"))
    )
    (net (code "166") (name "Net-(DS8-E)") (class "Default")
      (node (ref "DS8") (pin "1") (pinfunction "E_1") (pintype "passive"))
      (node (ref "R52") (pin "PAD_0") (pinfunction "PIN0_PAD_0") (pintype "passive"))
    )
    (net (code "167") (name "Net-(DS8-F)") (class "Default")
      (node (ref "DS8") (pin "9") (pinfunction "F_9") (pintype "passive"))
      (node (ref "R56") (pin "PAD_0") (pinfunction "PIN0_PAD_0") (pintype "passive"))
    )
    (net (code "168") (name "Net-(DS8-G)") (class "Default")
      (node (ref "DS8") (pin "10") (pinfunction "G_10") (pintype "passive"))
      (node (ref "R60") (pin "PAD_0") (pinfunction "PIN0_PAD_0") (pintype "passive"))
    )
    (net (code "169") (name "Net-(DS9-A)") (class "Default")
      (node (ref "DS9") (pin "7") (pinfunction "A_7") (pintype "passive"))
      (node (ref "R65") (pin "PAD_0") (pinfunction "PIN0_PAD_0") (pintype "passive"))
    )
    (net (code "170") (name "Net-(DS9-B)") (class "Default")
      (node (ref "DS9") (pin "6") (pinfunction "B_6") (pintype "passive"))
      (node (ref "R69") (pin "PAD_0") (pinfunction "PIN0_PAD_0") (pintype "passive"))
    )
    (net (code "171") (name "Net-(DS9-C)") (class "Default")
      (node (ref "DS9") (pin "4") (pinfunction "C_4") (pintype "passive"))
      (node (ref "R73") (pin "PAD_0") (pinfunction "PIN0_PAD_0") (pintype "passive"))
    )
    (net (code "172") (name "Net-(DS9-D)") (class "Default")
      (node (ref "DS9") (pin "2") (pinfunction "D_2") (pintype "passive"))
      (node (ref "R77") (pin "PAD_0") (pinfunction "PIN0_PAD_0") (pintype "passive"))
    )
    (net (code "173") (name "Net-(DS9-DOT)") (class "Default")
      (node (ref "DS9") (pin "5") (pinfunction "DOT_5") (pintype "passive"))
      (node (ref "R93") (pin "PAD_0") (pinfunction "PIN0_PAD_0") (pintype "passive"))
    )
    (net (code "174") (name "Net-(DS9-E)") (class "Default")
      (node (ref "DS9") (pin "1") (pinfunction "E_1") (pintype "passive"))
      (node (ref "R81") (pin "PAD_0") (pinfunction "PIN0_PAD_0") (pintype "passive"))
    )
    (net (code "175") (name "Net-(DS9-F)") (class "Default")
      (node (ref "DS9") (pin "9") (pinfunction "F_9") (pintype "passive"))
      (node (ref "R85") (pin "PAD_0") (pinfunction "PIN0_PAD_0") (pintype "passive"))
    )
    (net (code "176") (name "Net-(DS9-G)") (class "Default")
      (node (ref "DS9") (pin "10") (pinfunction "G_10") (pintype "passive"))
      (node (ref "R89") (pin "PAD_0") (pinfunction "PIN0_PAD_0") (pintype "passive"))
    )
    (net (code "177") (name "Net-(DS10-A)") (class "Default")
      (node (ref "DS10") (pin "7") (pinfunction "A_7") (pintype "passive"))
      (node (ref "R66") (pin "PAD_0") (pinfunction "PIN0_PAD_0") (pintype "passive"))
    )
    (net (code "178") (name "Net-(DS10-B)") (class "Default")
      (node (ref "DS10") (pin "6") (pinfunction "B_6") (pintype "passive"))
      (node (ref "R70") (pin "PAD_0") (pinfunction "PIN0_PAD_0") (pintype "passive"))
    )
    (net (code "179") (name "Net-(DS10-C)") (class "Default")
      (node (ref "DS10") (pin "4") (pinfunction "C_4") (pintype "passive"))
      (node (ref "R74") (pin "PAD_0") (pinfunction "PIN0_PAD_0") (pintype "passive"))
    )
    (net (code "180") (name "Net-(DS10-D)") (class "Default")
      (node (ref "DS10") (pin "2") (pinfunction "D_2") (pintype "passive"))
      (node (ref "R78") (pin "PAD_0") (pinfunction "PIN0_PAD_0") (pintype "passive"))
    )
    (net (code "181") (name "Net-(DS10-DOT)") (class "Default")
      (node (ref "DS10") (pin "5") (pinfunction "DOT_5") (pintype "passive"))
      (node (ref "R94") (pin "PAD_0") (pinfunction "PIN0_PAD_0") (pintype "passive"))
    )
    (net (code "182") (name "Net-(DS10-E)") (class "Default")
      (node (ref "DS10") (pin "1") (pinfunction "E_1") (pintype "passive"))
      (node (ref "R82") (pin "PAD_0") (pinfunction "PIN0_PAD_0") (pintype "passive"))
    )
    (net (code "183") (name "Net-(DS10-F)") (class "Default")
      (node (ref "DS10") (pin "9") (pinfunction "F_9") (pintype "passive"))
      (node (ref "R86") (pin "PAD_0") (pinfunction "PIN0_PAD_0") (pintype "passive"))
    )
    (net (code "184") (name "Net-(DS10-G)") (class "Default")
      (node (ref "DS10") (pin "10") (pinfunction "G_10") (pintype "passive"))
      (node (ref "R90") (pin "PAD_0") (pinfunction "PIN0_PAD_0") (pintype "passive"))
    )
    (net (code "185") (name "Net-(DS11-A)") (class "Default")
      (node (ref "DS11") (pin "7") (pinfunction "A_7") (pintype "passive"))
      (node (ref "R67") (pin "PAD_0") (pinfunction "PIN0_PAD_0") (pintype "passive"))
    )
    (net (code "186") (name "Net-(DS11-B)") (class "Default")
      (node (ref "DS11") (pin "6") (pinfunction "B_6") (pintype "passive"))
      (node (ref "R71") (pin "PAD_0") (pinfunction "PIN0_PAD_0") (pintype "passive"))
    )
    (net (code "187") (name "Net-(DS11-C)") (class "Default")
      (node (ref "DS11") (pin "4") (pinfunction "C_4") (pintype "passive"))
      (node (ref "R75") (pin "PAD_0") (pinfunction "PIN0_PAD_0") (pintype "passive"))
    )
    (net (code "188") (name "Net-(DS11-D)") (class "Default")
      (node (ref "DS11") (pin "2") (pinfunction "D_2") (pintype "passive"))
      (node (ref "R79") (pin "PAD_0") (pinfunction "PIN0_PAD_0") (pintype "passive"))
    )
    (net (code "189") (name "Net-(DS11-DOT)") (class "Default")
      (node (ref "DS11") (pin "5") (pinfunction "DOT_5") (pintype "passive"))
      (node (ref "R95") (pin "PAD_0") (pinfunction "PIN0_PAD_0") (pintype "passive"))
    )
    (net (code "190") (name "Net-(DS11-E)") (class "Default")
      (node (ref "DS11") (pin "1") (pinfunction "E_1") (pintype "passive"))
      (node (ref "R83") (pin "PAD_0") (pinfunction "PIN0_PAD_0") (pintype "passive"))
    )
    (net (code "191") (name "Net-(DS11-F)") (class "Default")
      (node (ref "DS11") (pin "9") (pinfunction "F_9") (pintype "passive"))
      (node (ref "R87") (pin "PAD_0") (pinfunction "PIN0_PAD_0") (pintype "passive"))
    )
    (net (code "192") (name "Net-(DS11-G)") (class "Default")
      (node (ref "DS11") (pin "10") (pinfunction "G_10") (pintype "passive"))
      (node (ref "R91") (pin "PAD_0") (pinfunction "PIN0_PAD_0") (pintype "passive"))
    )
    (net (code "193") (name "Net-(DS12-A)") (class "Default")
      (node (ref "DS12") (pin "7") (pinfunction "A_7") (pintype "passive"))
      (node (ref "R68") (pin "PAD_0") (pinfunction "PIN0_PAD_0") (pintype "passive"))
    )
    (net (code "194") (name "Net-(DS12-B)") (class "Default")
      (node (ref "DS12") (pin "6") (pinfunction "B_6") (pintype "passive"))
      (node (ref "R72") (pin "PAD_0") (pinfunction "PIN0_PAD_0") (pintype "passive"))
    )
    (net (code "195") (name "Net-(DS12-C)") (class "Default")
      (node (ref "DS12") (pin "4") (pinfunction "C_4") (pintype "passive"))
      (node (ref "R76") (pin "PAD_0") (pinfunction "PIN0_PAD_0") (pintype "passive"))
    )
    (net (code "196") (name "Net-(DS12-D)") (class "Default")
      (node (ref "DS12") (pin "2") (pinfunction "D_2") (pintype "passive"))
      (node (ref "R80") (pin "PAD_0") (pinfunction "PIN0_PAD_0") (pintype "passive"))
    )
    (net (code "197") (name "Net-(DS12-DOT)") (class "Default")
      (node (ref "DS12") (pin "5") (pinfunction "DOT_5") (pintype "passive"))
      (node (ref "R96") (pin "PAD_0") (pinfunction "PIN0_PAD_0") (pintype "passive"))
    )
    (net (code "198") (name "Net-(DS12-E)") (class "Default")
      (node (ref "DS12") (pin "1") (pinfunction "E_1") (pintype "passive"))
      (node (ref "R84") (pin "PAD_0") (pinfunction "PIN0_PAD_0") (pintype "passive"))
    )
    (net (code "199") (name "Net-(DS12-F)") (class "Default")
      (node (ref "DS12") (pin "9") (pinfunction "F_9") (pintype "passive"))
      (node (ref "R88") (pin "PAD_0") (pinfunction "PIN0_PAD_0") (pintype "passive"))
    )
    (net (code "200") (name "Net-(DS12-G)") (class "Default")
      (node (ref "DS12") (pin "10") (pinfunction "G_10") (pintype "passive"))
      (node (ref "R92") (pin "PAD_0") (pinfunction "PIN0_PAD_0") (pintype "passive"))
    )
    (net (code "201") (name "Net-(IC1-SER_IN)") (class "Default")
      (node (ref "IC1") (pin "14") (pinfunction "SER_IN_14") (pintype "bidirectional"))
      (node (ref "IC8") (pin "9") (pinfunction "SER_OUT_9") (pintype "bidirectional"))
    )
    (net (code "202") (name "Net-(IC1-SER_OUT)") (class "Default")
      (node (ref "IC1") (pin "9") (pinfunction "SER_OUT_9") (pintype "bidirectional"))
      (node (ref "IC2") (pin "14") (pinfunction "SER_IN_14") (pintype "bidirectional"))
    )
    (net (code "203") (name "Net-(IC2-SER_OUT)") (class "Default")
      (node (ref "IC2") (pin "9") (pinfunction "SER_OUT_9") (pintype "bidirectional"))
      (node (ref "IC3") (pin "14") (pinfunction "SER_IN_14") (pintype "bidirectional"))
    )
    (net (code "204") (name "Net-(IC3-SER_OUT)") (class "Default")
      (node (ref "IC3") (pin "9") (pinfunction "SER_OUT_9") (pintype "bidirectional"))
      (node (ref "IC4") (pin "14") (pinfunction "SER_IN_14") (pintype "bidirectional"))
    )
    (net (code "205") (name "Net-(IC5-SER_OUT)") (class "Default")
      (node (ref "IC5") (pin "9") (pinfunction "SER_OUT_9") (pintype "bidirectional"))
      (node (ref "IC6") (pin "14") (pinfunction "SER_IN_14") (pintype "bidirectional"))
    )
    (net (code "206") (name "Net-(IC6-SER_OUT)") (class "Default")
      (node (ref "IC6") (pin "9") (pinfunction "SER_OUT_9") (pintype "bidirectional"))
      (node (ref "IC7") (pin "14") (pinfunction "SER_IN_14") (pintype "bidirectional"))
    )
    (net (code "207") (name "Net-(IC7-SER_OUT)") (class "Default")
      (node (ref "IC7") (pin "9") (pinfunction "SER_OUT_9") (pintype "bidirectional"))
      (node (ref "IC8") (pin "14") (pinfunction "SER_IN_14") (pintype "bidirectional"))
    )
    (net (code "208") (name "Net-(IC10-SER_IN)") (class "Default")
      (node (ref "IC10") (pin "14") (pinfunction "SER_IN_14") (pintype "bidirectional"))
      (node (ref "IC9") (pin "9") (pinfunction "SER_OUT_9") (pintype "bidirectional"))
    )
    (net (code "209") (name "Net-(IC10-SER_OUT)") (class "Default")
      (node (ref "IC10") (pin "9") (pinfunction "SER_OUT_9") (pintype "bidirectional"))
      (node (ref "IC11") (pin "14") (pinfunction "SER_IN_14") (pintype "bidirectional"))
    )
    (net (code "210") (name "Net-(IC11-SER_OUT)") (class "Default")
      (node (ref "IC11") (pin "9") (pinfunction "SER_OUT_9") (pintype "bidirectional"))
      (node (ref "IC12") (pin "14") (pinfunction "SER_IN_14") (pintype "bidirectional"))
    )
    (net (code "211") (name "Net-(IC12-SER_OUT)") (class "Default")
      (node (ref "IC12") (pin "9") (pinfunction "SER_OUT_9") (pintype "bidirectional"))
      (node (ref "IC5") (pin "14") (pinfunction "SER_IN_14") (pintype "bidirectional"))
    )
    (net (code "212") (name "unconnected-(IC4-SER_OUT-Pad9)") (class "Default")
      (node (ref "IC4") (pin "9") (pinfunction "SER_OUT_9") (pintype "bidirectional"))
    )
  )
)
